# buck.net
KiCad netlist of a schematic drawn in EAGLE
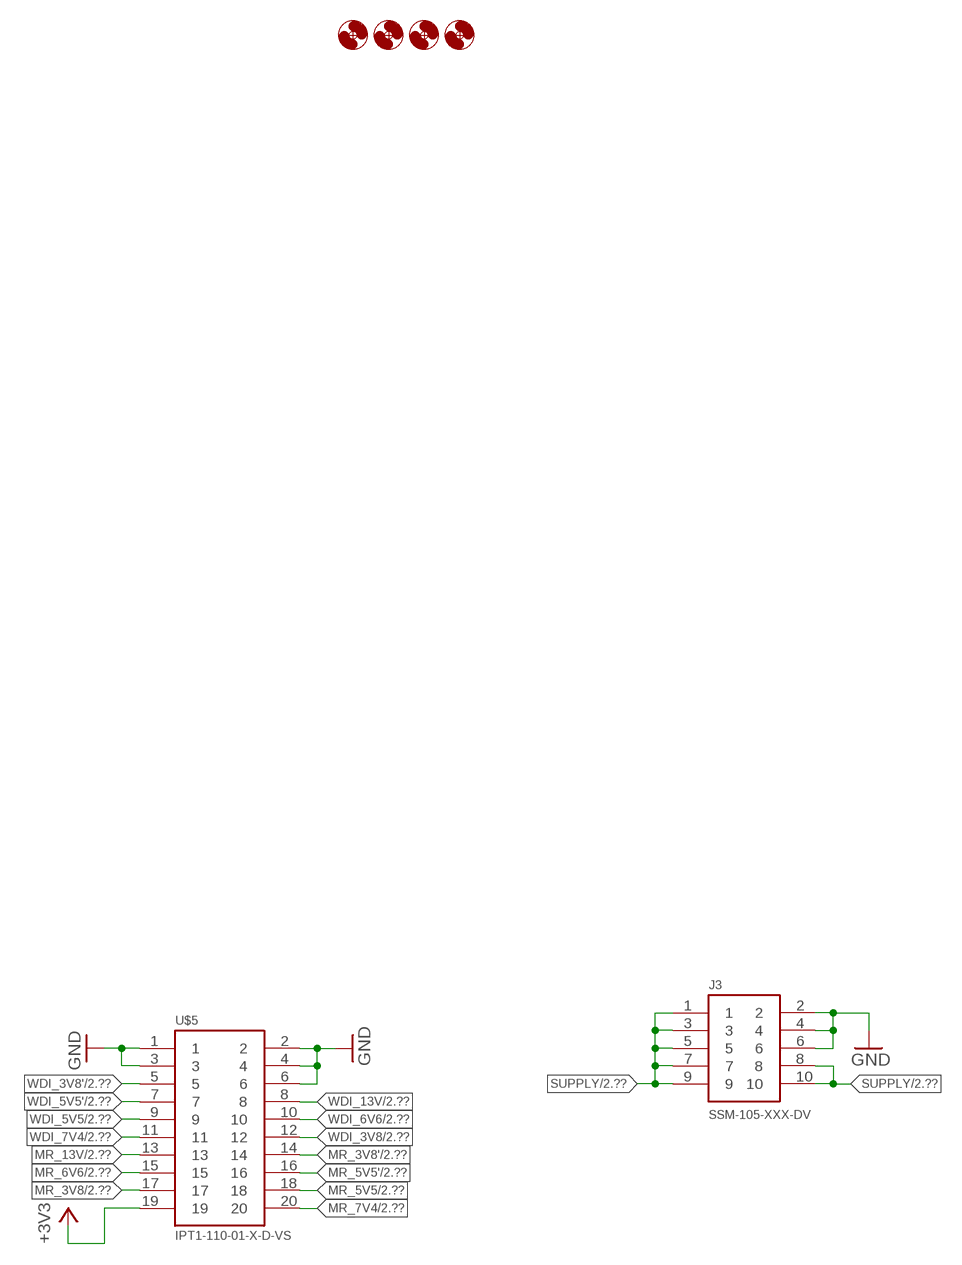
[diagram p0: schematic, sheet 1]
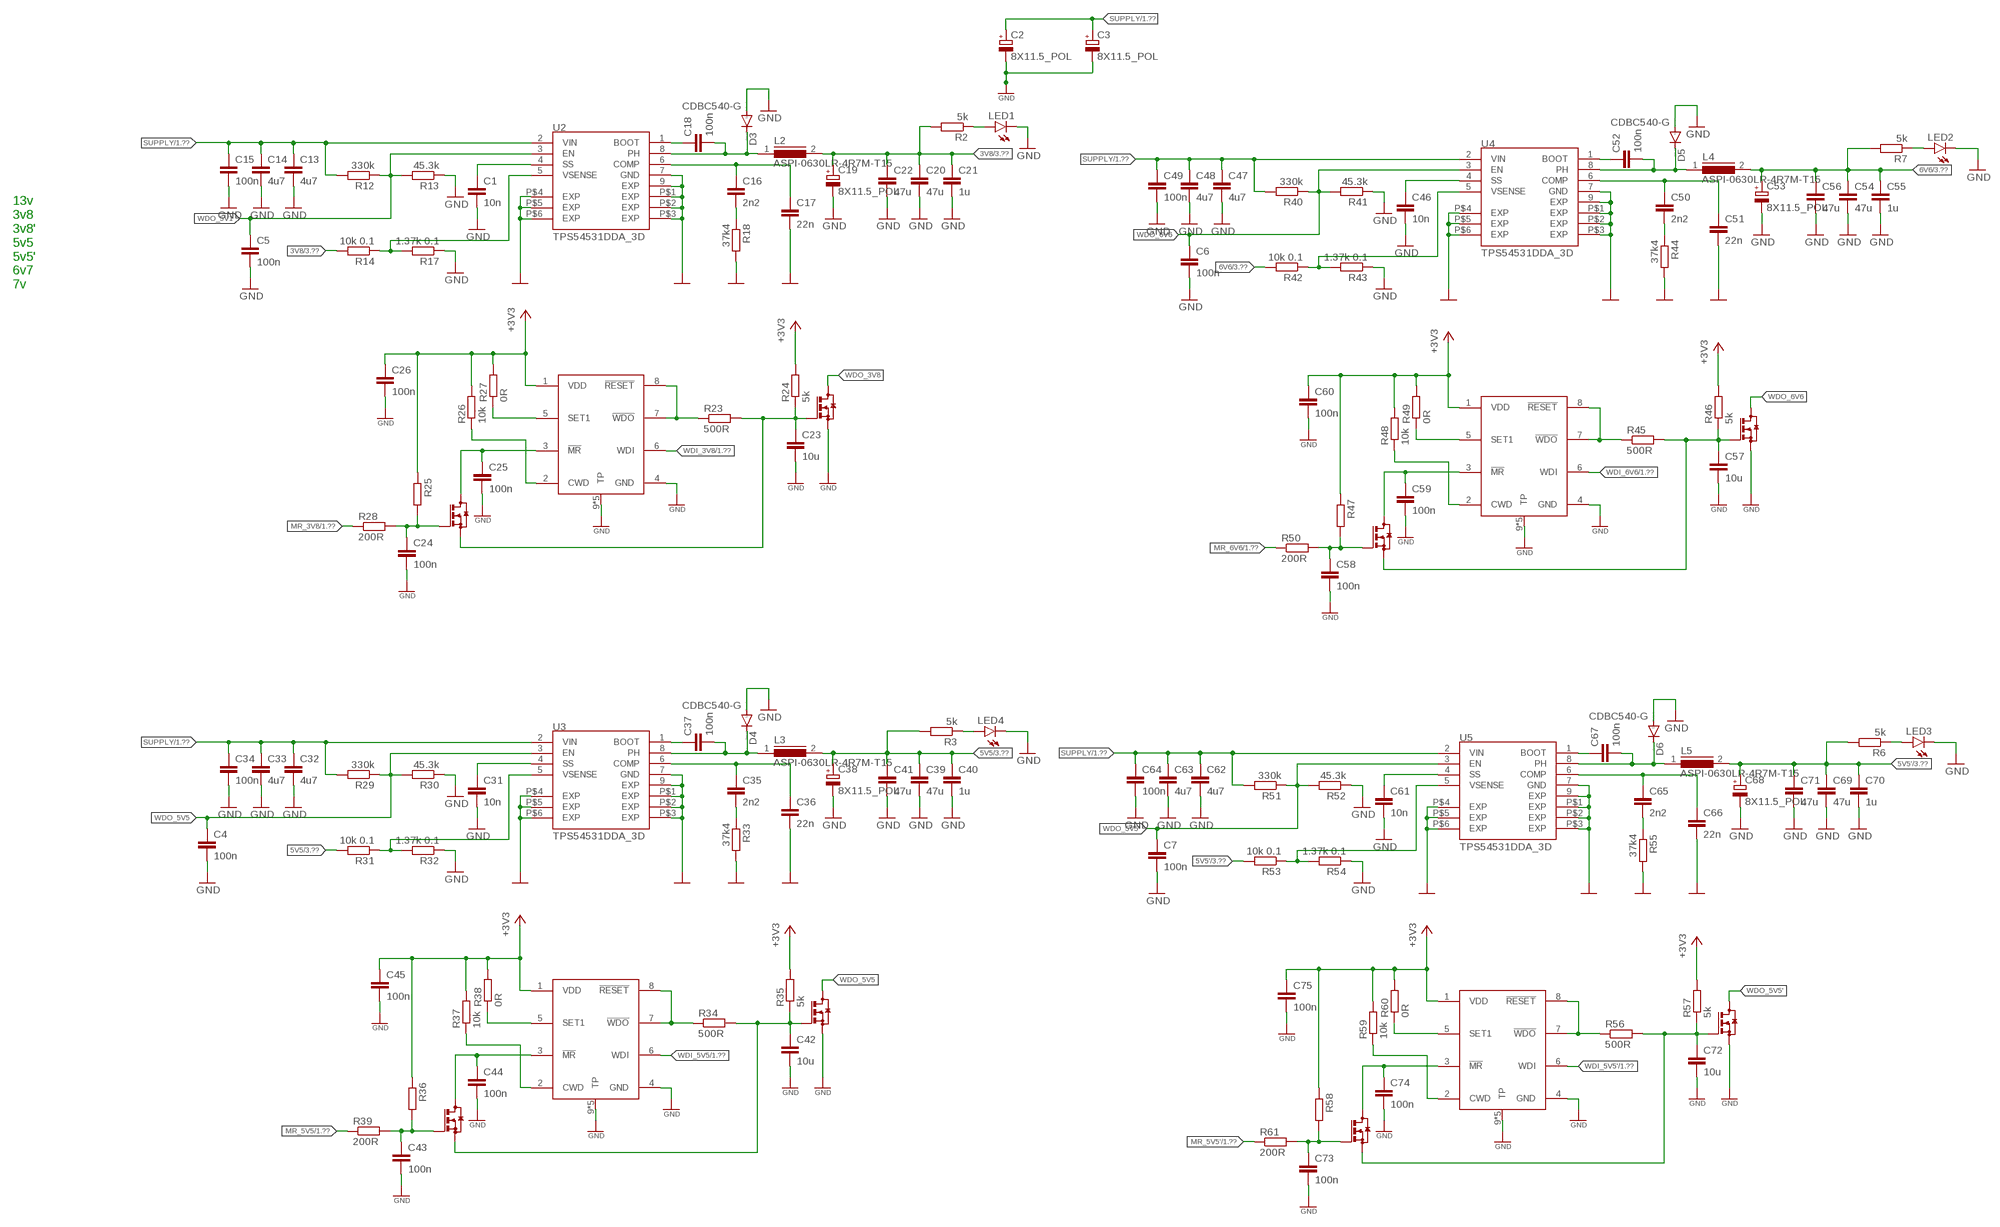
[diagram p1: schematic, sheet 2, part 1 of 2]
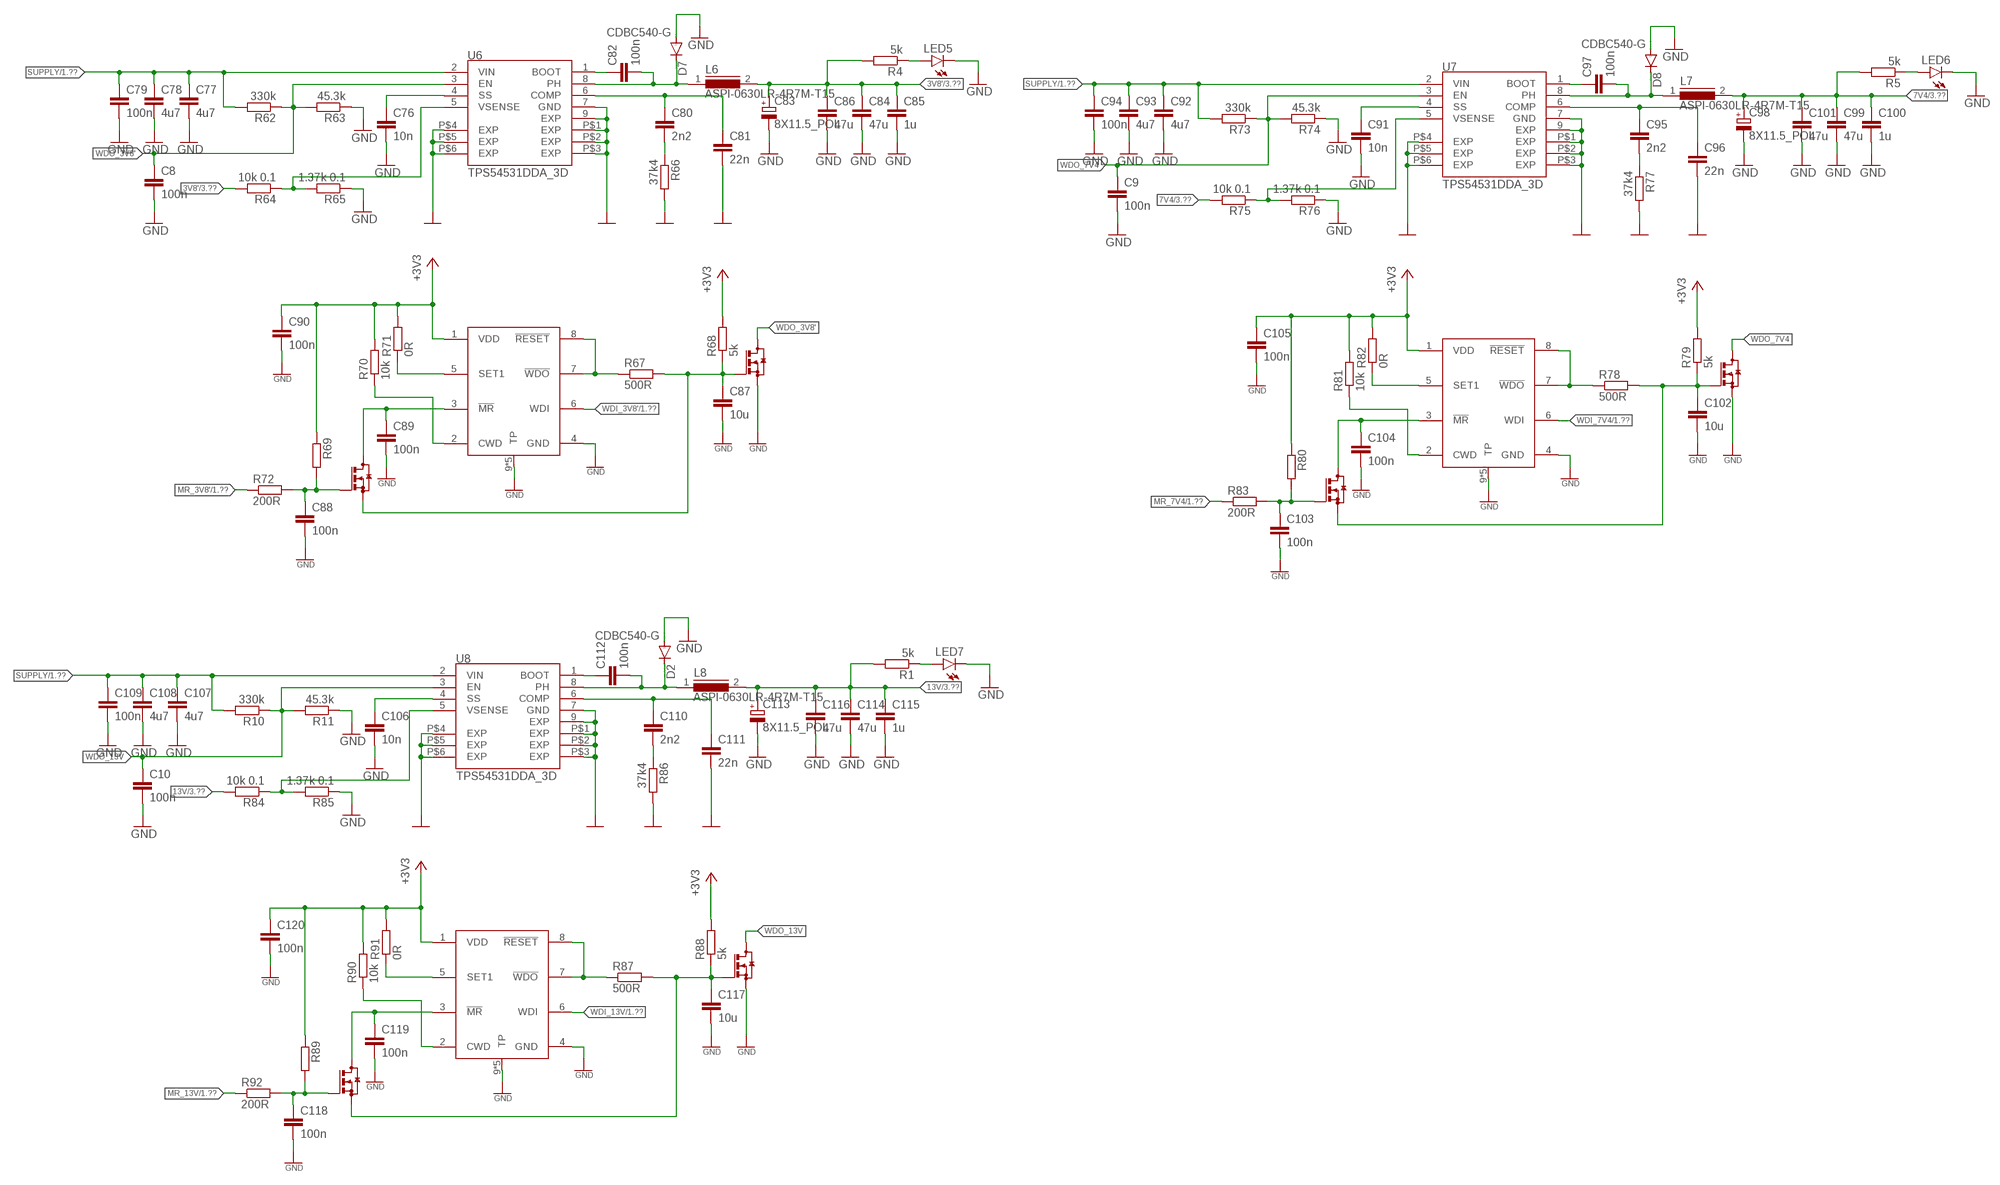
[diagram p2: schematic, sheet 2, part 2 of 2]
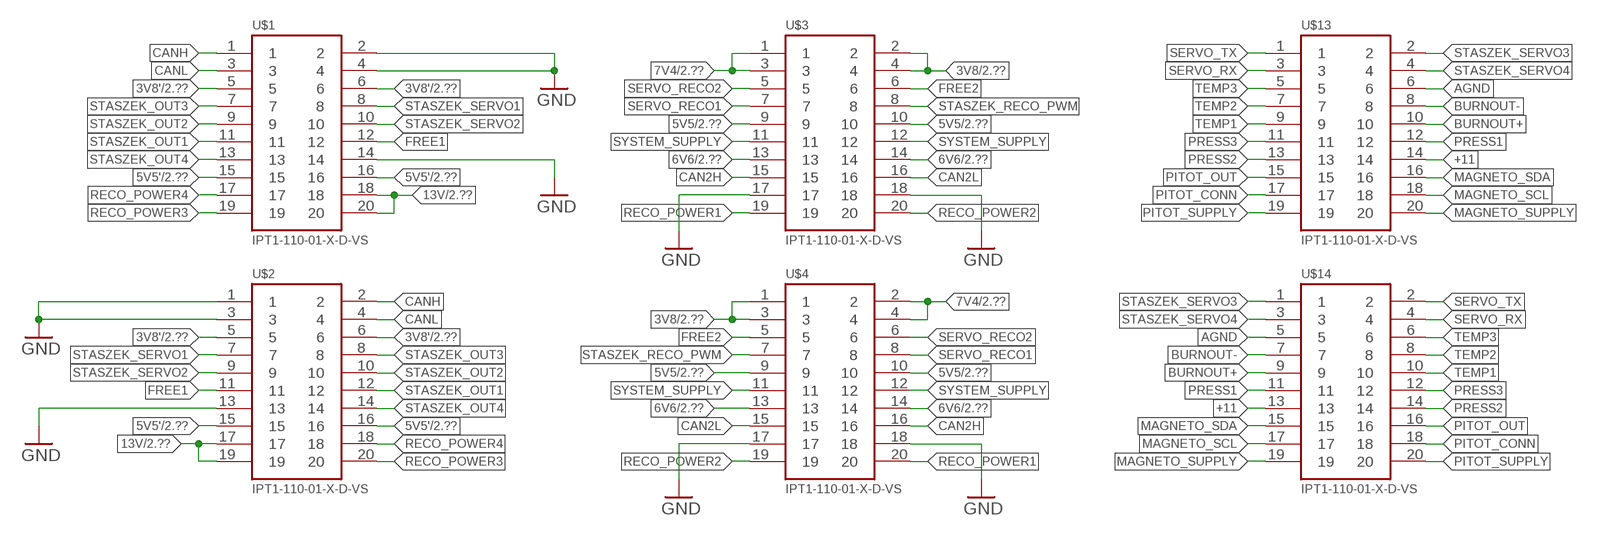
[diagram p3: schematic, sheet 3]

(export (version "E")
  (design (tool "Eeschema 10.0.6"))
  (components
    (comp (ref "U$1")
      (value "IPT1-110-01-X-D-VS")
      (footprint "eagle-import:IPT1-110-01-X-D-VS")
      (fields (field (name "MF") "Samtec") (field (name "MP") "IPT1-110--01-S-D-VS-"))
      (libsource (lib "eagle-import") (part "IPT1-110-01-X-D-VS"))
    )
    (comp (ref "U$2")
      (value "IPT1-110-01-X-D-VS")
      (footprint "eagle-import:IPT1-110-01-X-D-VS")
      (fields (field (name "MF") "Samtec") (field (name "MP") "IPT1-110--01-S-D-VS-"))
      (libsource (lib "eagle-import") (part "IPT1-110-01-X-D-VS"))
    )
    (comp (ref "U$3")
      (value "IPT1-110-01-X-D-VS")
      (footprint "eagle-import:IPT1-110-01-X-D-VS")
      (fields (field (name "MF") "Samtec") (field (name "MP") "IPT1-110--01-S-D-VS-"))
      (libsource (lib "eagle-import") (part "IPT1-110-01-X-D-VS"))
    )
    (comp (ref "U$4")
      (value "IPT1-110-01-X-D-VS")
      (footprint "eagle-import:IPT1-110-01-X-D-VS")
      (fields (field (name "MF") "Samtec") (field (name "MP") "IPT1-110--01-S-D-VS-"))
      (libsource (lib "eagle-import") (part "IPT1-110-01-X-D-VS"))
    )
    (comp (ref "U$13")
      (value "IPT1-110-01-X-D-VS")
      (footprint "eagle-import:IPT1-110-01-X-D-VS")
      (fields (field (name "MF") "Samtec") (field (name "MP") "IPT1-110--01-S-D-VS-"))
      (libsource (lib "eagle-import") (part "IPT1-110-01-X-D-VS"))
    )
    (comp (ref "U$14")
      (value "IPT1-110-01-X-D-VS")
      (footprint "eagle-import:IPT1-110-01-X-D-VS")
      (fields (field (name "MF") "Samtec") (field (name "MP") "IPT1-110--01-S-D-VS-"))
      (libsource (lib "eagle-import") (part "IPT1-110-01-X-D-VS"))
    )
    (comp (ref "H1")
      (value "MOUNT-HOLE3.2")
      (footprint "eagle-import:3,2")
      (libsource (lib "eagle-import") (part "MOUNT-HOLE3.2"))
    )
    (comp (ref "H2")
      (value "MOUNT-HOLE3.2")
      (footprint "eagle-import:3,2")
      (libsource (lib "eagle-import") (part "MOUNT-HOLE3.2"))
    )
    (comp (ref "H3")
      (value "MOUNT-HOLE3.2")
      (footprint "eagle-import:3,2")
      (libsource (lib "eagle-import") (part "MOUNT-HOLE3.2"))
    )
    (comp (ref "H4")
      (value "MOUNT-HOLE3.2")
      (footprint "eagle-import:3,2")
      (libsource (lib "eagle-import") (part "MOUNT-HOLE3.2"))
    )
    (comp (ref "J3")
      (value "SSM-105-XXX-DV")
      (footprint "eagle-import:SSM-105-XXX-DV")
      (fields (field (name "MF") "Samtec"))
      (libsource (lib "eagle-import") (part "SSM-105-XXX-DV"))
    )
    (comp (ref "U$5")
      (value "IPT1-110-01-X-D-VS")
      (footprint "eagle-import:IPT1-110-01-X-D-VS")
      (fields (field (name "MF") "Samtec") (field (name "MP") "IPT1-110--01-S-D-VS-"))
      (libsource (lib "eagle-import") (part "IPT1-110-01-X-D-VS"))
    )
    (comp (ref "C1")
      (value "10n")
      (footprint "eagle-import:C0603K")
      (libsource (lib "eagle-import") (part "C-EUC0603K"))
    )
    (comp (ref "C2")
      (value "8X11.5_POL")
      (footprint "eagle-import:CAPPRD350W65D800H1150A")
      (libsource (lib "eagle-import") (part "8X11.5_POL"))
    )
    (comp (ref "C3")
      (value "8X11.5_POL")
      (footprint "eagle-import:CAPPRD350W65D800H1150A")
      (libsource (lib "eagle-import") (part "8X11.5_POL"))
    )
    (comp (ref "C4")
      (value "100n")
      (footprint "eagle-import:C0603K")
      (libsource (lib "eagle-import") (part "C-EUC0603K"))
    )
    (comp (ref "C5")
      (value "100n")
      (footprint "eagle-import:C0603K")
      (libsource (lib "eagle-import") (part "C-EUC0603K"))
    )
    (comp (ref "C6")
      (value "100n")
      (footprint "eagle-import:C0603K")
      (libsource (lib "eagle-import") (part "C-EUC0603K"))
    )
    (comp (ref "C7")
      (value "100n")
      (footprint "eagle-import:C0603K")
      (libsource (lib "eagle-import") (part "C-EUC0603K"))
    )
    (comp (ref "C8")
      (value "100n")
      (footprint "eagle-import:C0603K")
      (libsource (lib "eagle-import") (part "C-EUC0603K"))
    )
    (comp (ref "C9")
      (value "100n")
      (footprint "eagle-import:C0603K")
      (libsource (lib "eagle-import") (part "C-EUC0603K"))
    )
    (comp (ref "C10")
      (value "100n")
      (footprint "eagle-import:C0603K")
      (libsource (lib "eagle-import") (part "C-EUC0603K"))
    )
    (comp (ref "C13")
      (value "4u7")
      (footprint "eagle-import:C0805K")
      (libsource (lib "eagle-import") (part "C-EUC0805K"))
    )
    (comp (ref "C14")
      (value "4u7")
      (footprint "eagle-import:C0805K")
      (libsource (lib "eagle-import") (part "C-EUC0805K"))
    )
    (comp (ref "C15")
      (value "100n")
      (footprint "eagle-import:C0603K")
      (libsource (lib "eagle-import") (part "C-EUC0603K"))
    )
    (comp (ref "C16")
      (value "2n2")
      (footprint "eagle-import:C0603K")
      (libsource (lib "eagle-import") (part "C-EUC0603K"))
    )
    (comp (ref "C17")
      (value "22n")
      (footprint "eagle-import:C0603K")
      (libsource (lib "eagle-import") (part "C-EUC0603K"))
    )
    (comp (ref "C18")
      (value "100n")
      (footprint "eagle-import:C0603K")
      (libsource (lib "eagle-import") (part "C-EUC0603K"))
    )
    (comp (ref "C19")
      (value "8X11.5_POL")
      (footprint "eagle-import:CAPPRD350W65D800H1150A")
      (libsource (lib "eagle-import") (part "8X11.5_POL"))
    )
    (comp (ref "C20")
      (value "47u")
      (footprint "eagle-import:C1210")
      (libsource (lib "eagle-import") (part "C-EUC1210"))
    )
    (comp (ref "C21")
      (value "1u")
      (footprint "eagle-import:C0603K")
      (libsource (lib "eagle-import") (part "C-EUC0603K"))
    )
    (comp (ref "C22")
      (value "47u")
      (footprint "eagle-import:C1210")
      (libsource (lib "eagle-import") (part "C-EUC1210"))
    )
    (comp (ref "C23")
      (value "10u")
      (footprint "eagle-import:C0805K")
      (libsource (lib "eagle-import") (part "C-EUC0805K"))
    )
    (comp (ref "C24")
      (value "100n")
      (footprint "eagle-import:C0603K")
      (libsource (lib "eagle-import") (part "C-EUC0603K"))
    )
    (comp (ref "C25")
      (value "100n")
      (footprint "eagle-import:C0603K")
      (libsource (lib "eagle-import") (part "C-EUC0603K"))
    )
    (comp (ref "C26")
      (value "100n")
      (footprint "eagle-import:C0603K")
      (libsource (lib "eagle-import") (part "C-EUC0603K"))
    )
    (comp (ref "C31")
      (value "10n")
      (footprint "eagle-import:C0603K")
      (libsource (lib "eagle-import") (part "C-EUC0603K"))
    )
    (comp (ref "C32")
      (value "4u7")
      (footprint "eagle-import:C0805K")
      (libsource (lib "eagle-import") (part "C-EUC0805K"))
    )
    (comp (ref "C33")
      (value "4u7")
      (footprint "eagle-import:C0805K")
      (libsource (lib "eagle-import") (part "C-EUC0805K"))
    )
    (comp (ref "C34")
      (value "100n")
      (footprint "eagle-import:C0603K")
      (libsource (lib "eagle-import") (part "C-EUC0603K"))
    )
    (comp (ref "C35")
      (value "2n2")
      (footprint "eagle-import:C0603K")
      (libsource (lib "eagle-import") (part "C-EUC0603K"))
    )
    (comp (ref "C36")
      (value "22n")
      (footprint "eagle-import:C0603K")
      (libsource (lib "eagle-import") (part "C-EUC0603K"))
    )
    (comp (ref "C37")
      (value "100n")
      (footprint "eagle-import:C0603K")
      (libsource (lib "eagle-import") (part "C-EUC0603K"))
    )
    (comp (ref "C38")
      (value "8X11.5_POL")
      (footprint "eagle-import:CAPPRD350W65D800H1150A")
      (libsource (lib "eagle-import") (part "8X11.5_POL"))
    )
    (comp (ref "C39")
      (value "47u")
      (footprint "eagle-import:C1210")
      (libsource (lib "eagle-import") (part "C-EUC1210"))
    )
    (comp (ref "C40")
      (value "1u")
      (footprint "eagle-import:C0603K")
      (libsource (lib "eagle-import") (part "C-EUC0603K"))
    )
    (comp (ref "C41")
      (value "47u")
      (footprint "eagle-import:C1210")
      (libsource (lib "eagle-import") (part "C-EUC1210"))
    )
    (comp (ref "C42")
      (value "10u")
      (footprint "eagle-import:C0805K")
      (libsource (lib "eagle-import") (part "C-EUC0805K"))
    )
    (comp (ref "C43")
      (value "100n")
      (footprint "eagle-import:C0603K")
      (libsource (lib "eagle-import") (part "C-EUC0603K"))
    )
    (comp (ref "C44")
      (value "100n")
      (footprint "eagle-import:C0603K")
      (libsource (lib "eagle-import") (part "C-EUC0603K"))
    )
    (comp (ref "C45")
      (value "100n")
      (footprint "eagle-import:C0603K")
      (libsource (lib "eagle-import") (part "C-EUC0603K"))
    )
    (comp (ref "C46")
      (value "10n")
      (footprint "eagle-import:C0603K")
      (libsource (lib "eagle-import") (part "C-EUC0603K"))
    )
    (comp (ref "C47")
      (value "4u7")
      (footprint "eagle-import:C0805K")
      (libsource (lib "eagle-import") (part "C-EUC0805K"))
    )
    (comp (ref "C48")
      (value "4u7")
      (footprint "eagle-import:C0805K")
      (libsource (lib "eagle-import") (part "C-EUC0805K"))
    )
    (comp (ref "C49")
      (value "100n")
      (footprint "eagle-import:C0603K")
      (libsource (lib "eagle-import") (part "C-EUC0603K"))
    )
    (comp (ref "C50")
      (value "2n2")
      (footprint "eagle-import:C0603K")
      (libsource (lib "eagle-import") (part "C-EUC0603K"))
    )
    (comp (ref "C51")
      (value "22n")
      (footprint "eagle-import:C0603K")
      (libsource (lib "eagle-import") (part "C-EUC0603K"))
    )
    (comp (ref "C52")
      (value "100n")
      (footprint "eagle-import:C0603K")
      (libsource (lib "eagle-import") (part "C-EUC0603K"))
    )
    (comp (ref "C53")
      (value "8X11.5_POL")
      (footprint "eagle-import:CAPPRD350W65D800H1150A")
      (libsource (lib "eagle-import") (part "8X11.5_POL"))
    )
    (comp (ref "C54")
      (value "47u")
      (footprint "eagle-import:C1210")
      (libsource (lib "eagle-import") (part "C-EUC1210"))
    )
    (comp (ref "C55")
      (value "1u")
      (footprint "eagle-import:C0603K")
      (libsource (lib "eagle-import") (part "C-EUC0603K"))
    )
    (comp (ref "C56")
      (value "47u")
      (footprint "eagle-import:C1210")
      (libsource (lib "eagle-import") (part "C-EUC1210"))
    )
    (comp (ref "C57")
      (value "10u")
      (footprint "eagle-import:C0805K")
      (libsource (lib "eagle-import") (part "C-EUC0805K"))
    )
    (comp (ref "C58")
      (value "100n")
      (footprint "eagle-import:C0603K")
      (libsource (lib "eagle-import") (part "C-EUC0603K"))
    )
    (comp (ref "C59")
      (value "100n")
      (footprint "eagle-import:C0603K")
      (libsource (lib "eagle-import") (part "C-EUC0603K"))
    )
    (comp (ref "C60")
      (value "100n")
      (footprint "eagle-import:C0603K")
      (libsource (lib "eagle-import") (part "C-EUC0603K"))
    )
    (comp (ref "C61")
      (value "10n")
      (footprint "eagle-import:C0603K")
      (libsource (lib "eagle-import") (part "C-EUC0603K"))
    )
    (comp (ref "C62")
      (value "4u7")
      (footprint "eagle-import:C0805K")
      (libsource (lib "eagle-import") (part "C-EUC0805K"))
    )
    (comp (ref "C63")
      (value "4u7")
      (footprint "eagle-import:C0805K")
      (libsource (lib "eagle-import") (part "C-EUC0805K"))
    )
    (comp (ref "C64")
      (value "100n")
      (footprint "eagle-import:C0603K")
      (libsource (lib "eagle-import") (part "C-EUC0603K"))
    )
    (comp (ref "C65")
      (value "2n2")
      (footprint "eagle-import:C0603K")
      (libsource (lib "eagle-import") (part "C-EUC0603K"))
    )
    (comp (ref "C66")
      (value "22n")
      (footprint "eagle-import:C0603K")
      (libsource (lib "eagle-import") (part "C-EUC0603K"))
    )
    (comp (ref "C67")
      (value "100n")
      (footprint "eagle-import:C0603K")
      (libsource (lib "eagle-import") (part "C-EUC0603K"))
    )
    (comp (ref "C68")
      (value "8X11.5_POL")
      (footprint "eagle-import:CAPPRD350W65D800H1150A")
      (libsource (lib "eagle-import") (part "8X11.5_POL"))
    )
    (comp (ref "C69")
      (value "47u")
      (footprint "eagle-import:C1210")
      (libsource (lib "eagle-import") (part "C-EUC1210"))
    )
    (comp (ref "C70")
      (value "1u")
      (footprint "eagle-import:C0603K")
      (libsource (lib "eagle-import") (part "C-EUC0603K"))
    )
    (comp (ref "C71")
      (value "47u")
      (footprint "eagle-import:C1210")
      (libsource (lib "eagle-import") (part "C-EUC1210"))
    )
    (comp (ref "C72")
      (value "10u")
      (footprint "eagle-import:C0805K")
      (libsource (lib "eagle-import") (part "C-EUC0805K"))
    )
    (comp (ref "C73")
      (value "100n")
      (footprint "eagle-import:C0603K")
      (libsource (lib "eagle-import") (part "C-EUC0603K"))
    )
    (comp (ref "C74")
      (value "100n")
      (footprint "eagle-import:C0603K")
      (libsource (lib "eagle-import") (part "C-EUC0603K"))
    )
    (comp (ref "C75")
      (value "100n")
      (footprint "eagle-import:C0603K")
      (libsource (lib "eagle-import") (part "C-EUC0603K"))
    )
    (comp (ref "C76")
      (value "10n")
      (footprint "eagle-import:C0603K")
      (libsource (lib "eagle-import") (part "C-EUC0603K"))
    )
    (comp (ref "C77")
      (value "4u7")
      (footprint "eagle-import:C0805K")
      (libsource (lib "eagle-import") (part "C-EUC0805K"))
    )
    (comp (ref "C78")
      (value "4u7")
      (footprint "eagle-import:C0805K")
      (libsource (lib "eagle-import") (part "C-EUC0805K"))
    )
    (comp (ref "C79")
      (value "100n")
      (footprint "eagle-import:C0603K")
      (libsource (lib "eagle-import") (part "C-EUC0603K"))
    )
    (comp (ref "C80")
      (value "2n2")
      (footprint "eagle-import:C0603K")
      (libsource (lib "eagle-import") (part "C-EUC0603K"))
    )
    (comp (ref "C81")
      (value "22n")
      (footprint "eagle-import:C0603K")
      (libsource (lib "eagle-import") (part "C-EUC0603K"))
    )
    (comp (ref "C82")
      (value "100n")
      (footprint "eagle-import:C0603K")
      (libsource (lib "eagle-import") (part "C-EUC0603K"))
    )
    (comp (ref "C83")
      (value "8X11.5_POL")
      (footprint "eagle-import:CAPPRD350W65D800H1150A")
      (libsource (lib "eagle-import") (part "8X11.5_POL"))
    )
    (comp (ref "C84")
      (value "47u")
      (footprint "eagle-import:C1210")
      (libsource (lib "eagle-import") (part "C-EUC1210"))
    )
    (comp (ref "C85")
      (value "1u")
      (footprint "eagle-import:C0603K")
      (libsource (lib "eagle-import") (part "C-EUC0603K"))
    )
    (comp (ref "C86")
      (value "47u")
      (footprint "eagle-import:C1210")
      (libsource (lib "eagle-import") (part "C-EUC1210"))
    )
    (comp (ref "C87")
      (value "10u")
      (footprint "eagle-import:C0805K")
      (libsource (lib "eagle-import") (part "C-EUC0805K"))
    )
    (comp (ref "C88")
      (value "100n")
      (footprint "eagle-import:C0603K")
      (libsource (lib "eagle-import") (part "C-EUC0603K"))
    )
    (comp (ref "C89")
      (value "100n")
      (footprint "eagle-import:C0603K")
      (libsource (lib "eagle-import") (part "C-EUC0603K"))
    )
    (comp (ref "C90")
      (value "100n")
      (footprint "eagle-import:C0603K")
      (libsource (lib "eagle-import") (part "C-EUC0603K"))
    )
    (comp (ref "C91")
      (value "10n")
      (footprint "eagle-import:C0603K")
      (libsource (lib "eagle-import") (part "C-EUC0603K"))
    )
    (comp (ref "C92")
      (value "4u7")
      (footprint "eagle-import:C0805K")
      (libsource (lib "eagle-import") (part "C-EUC0805K"))
    )
    (comp (ref "C93")
      (value "4u7")
      (footprint "eagle-import:C0805K")
      (libsource (lib "eagle-import") (part "C-EUC0805K"))
    )
    (comp (ref "C94")
      (value "100n")
      (footprint "eagle-import:C0603K")
      (libsource (lib "eagle-import") (part "C-EUC0603K"))
    )
    (comp (ref "C95")
      (value "2n2")
      (footprint "eagle-import:C0603K")
      (libsource (lib "eagle-import") (part "C-EUC0603K"))
    )
    (comp (ref "C96")
      (value "22n")
      (footprint "eagle-import:C0603K")
      (libsource (lib "eagle-import") (part "C-EUC0603K"))
    )
    (comp (ref "C97")
      (value "100n")
      (footprint "eagle-import:C0603K")
      (libsource (lib "eagle-import") (part "C-EUC0603K"))
    )
    (comp (ref "C98")
      (value "8X11.5_POL")
      (footprint "eagle-import:CAPPRD350W65D800H1150A")
      (libsource (lib "eagle-import") (part "8X11.5_POL"))
    )
    (comp (ref "C99")
      (value "47u")
      (footprint "eagle-import:C1210")
      (libsource (lib "eagle-import") (part "C-EUC1210"))
    )
    (comp (ref "C100")
      (value "1u")
      (footprint "eagle-import:C0603K")
      (libsource (lib "eagle-import") (part "C-EUC0603K"))
    )
    (comp (ref "C101")
      (value "47u")
      (footprint "eagle-import:C1210")
      (libsource (lib "eagle-import") (part "C-EUC1210"))
    )
    (comp (ref "C102")
      (value "10u")
      (footprint "eagle-import:C0805K")
      (libsource (lib "eagle-import") (part "C-EUC0805K"))
    )
    (comp (ref "C103")
      (value "100n")
      (footprint "eagle-import:C0603K")
      (libsource (lib "eagle-import") (part "C-EUC0603K"))
    )
    (comp (ref "C104")
      (value "100n")
      (footprint "eagle-import:C0603K")
      (libsource (lib "eagle-import") (part "C-EUC0603K"))
    )
    (comp (ref "C105")
      (value "100n")
      (footprint "eagle-import:C0603K")
      (libsource (lib "eagle-import") (part "C-EUC0603K"))
    )
    (comp (ref "C106")
      (value "10n")
      (footprint "eagle-import:C0603K")
      (libsource (lib "eagle-import") (part "C-EUC0603K"))
    )
    (comp (ref "C107")
      (value "4u7")
      (footprint "eagle-import:C0805K")
      (libsource (lib "eagle-import") (part "C-EUC0805K"))
    )
    (comp (ref "C108")
      (value "4u7")
      (footprint "eagle-import:C0805K")
      (libsource (lib "eagle-import") (part "C-EUC0805K"))
    )
    (comp (ref "C109")
      (value "100n")
      (footprint "eagle-import:C0603K")
      (libsource (lib "eagle-import") (part "C-EUC0603K"))
    )
    (comp (ref "C110")
      (value "2n2")
      (footprint "eagle-import:C0603K")
      (libsource (lib "eagle-import") (part "C-EUC0603K"))
    )
    (comp (ref "C111")
      (value "22n")
      (footprint "eagle-import:C0603K")
      (libsource (lib "eagle-import") (part "C-EUC0603K"))
    )
    (comp (ref "C112")
      (value "100n")
      (footprint "eagle-import:C0603K")
      (libsource (lib "eagle-import") (part "C-EUC0603K"))
    )
    (comp (ref "C113")
      (value "8X11.5_POL")
      (footprint "eagle-import:CAPPRD350W65D800H1150A")
      (libsource (lib "eagle-import") (part "8X11.5_POL"))
    )
    (comp (ref "C114")
      (value "47u")
      (footprint "eagle-import:C1210")
      (libsource (lib "eagle-import") (part "C-EUC1210"))
    )
    (comp (ref "C115")
      (value "1u")
      (footprint "eagle-import:C0603K")
      (libsource (lib "eagle-import") (part "C-EUC0603K"))
    )
    (comp (ref "C116")
      (value "47u")
      (footprint "eagle-import:C1210")
      (libsource (lib "eagle-import") (part "C-EUC1210"))
    )
    (comp (ref "C117")
      (value "10u")
      (footprint "eagle-import:C0805K")
      (libsource (lib "eagle-import") (part "C-EUC0805K"))
    )
    (comp (ref "C118")
      (value "100n")
      (footprint "eagle-import:C0603K")
      (libsource (lib "eagle-import") (part "C-EUC0603K"))
    )
    (comp (ref "C119")
      (value "100n")
      (footprint "eagle-import:C0603K")
      (libsource (lib "eagle-import") (part "C-EUC0603K"))
    )
    (comp (ref "C120")
      (value "100n")
      (footprint "eagle-import:C0603K")
      (libsource (lib "eagle-import") (part "C-EUC0603K"))
    )
    (comp (ref "D2")
      (value "CDBC540-G")
      (footprint "eagle-import:SMC")
      (libsource (lib "eagle-import") (part "DIODE-SMC"))
    )
    (comp (ref "D3")
      (value "CDBC540-G")
      (footprint "eagle-import:SMC")
      (libsource (lib "eagle-import") (part "DIODE-SMC"))
    )
    (comp (ref "D4")
      (value "CDBC540-G")
      (footprint "eagle-import:SMC")
      (libsource (lib "eagle-import") (part "DIODE-SMC"))
    )
    (comp (ref "D5")
      (value "CDBC540-G")
      (footprint "eagle-import:SMC")
      (libsource (lib "eagle-import") (part "DIODE-SMC"))
    )
    (comp (ref "D6")
      (value "CDBC540-G")
      (footprint "eagle-import:SMC")
      (libsource (lib "eagle-import") (part "DIODE-SMC"))
    )
    (comp (ref "D7")
      (value "CDBC540-G")
      (footprint "eagle-import:SMC")
      (libsource (lib "eagle-import") (part "DIODE-SMC"))
    )
    (comp (ref "D8")
      (value "CDBC540-G")
      (footprint "eagle-import:SMC")
      (libsource (lib "eagle-import") (part "DIODE-SMC"))
    )
    (comp (ref "L2")
      (value "ASPI-0630LR-4R7M-T15")
      (footprint "eagle-import:DR74")
      (libsource (lib "eagle-import") (part "DR74"))
    )
    (comp (ref "L3")
      (value "ASPI-0630LR-4R7M-T15")
      (footprint "eagle-import:DR74")
      (libsource (lib "eagle-import") (part "DR74"))
    )
    (comp (ref "L4")
      (value "ASPI-0630LR-4R7M-T15")
      (footprint "eagle-import:DR74")
      (libsource (lib "eagle-import") (part "DR74"))
    )
    (comp (ref "L5")
      (value "ASPI-0630LR-4R7M-T15")
      (footprint "eagle-import:DR74")
      (libsource (lib "eagle-import") (part "DR74"))
    )
    (comp (ref "L6")
      (value "ASPI-0630LR-4R7M-T15")
      (footprint "eagle-import:DR74")
      (libsource (lib "eagle-import") (part "DR74"))
    )
    (comp (ref "L7")
      (value "ASPI-0630LR-4R7M-T15")
      (footprint "eagle-import:DR74")
      (libsource (lib "eagle-import") (part "DR74"))
    )
    (comp (ref "L8")
      (value "ASPI-0630LR-4R7M-T15")
      (footprint "eagle-import:DR74")
      (libsource (lib "eagle-import") (part "DR74"))
    )
    (comp (ref "LED1")
      (value "LEDCHIPLED_0603")
      (footprint "eagle-import:CHIPLED_0603")
      (libsource (lib "eagle-import") (part "LEDCHIPLED_0603"))
    )
    (comp (ref "LED2")
      (value "LEDCHIPLED_0603")
      (footprint "eagle-import:CHIPLED_0603")
      (libsource (lib "eagle-import") (part "LEDCHIPLED_0603"))
    )
    (comp (ref "LED3")
      (value "LEDCHIPLED_0603")
      (footprint "eagle-import:CHIPLED_0603")
      (libsource (lib "eagle-import") (part "LEDCHIPLED_0603"))
    )
    (comp (ref "LED4")
      (value "LEDCHIPLED_0603")
      (footprint "eagle-import:CHIPLED_0603")
      (libsource (lib "eagle-import") (part "LEDCHIPLED_0603"))
    )
    (comp (ref "LED5")
      (value "LEDCHIPLED_0603")
      (footprint "eagle-import:CHIPLED_0603")
      (libsource (lib "eagle-import") (part "LEDCHIPLED_0603"))
    )
    (comp (ref "LED6")
      (value "LEDCHIPLED_0603")
      (footprint "eagle-import:CHIPLED_0603")
      (libsource (lib "eagle-import") (part "LEDCHIPLED_0603"))
    )
    (comp (ref "LED7")
      (value "LEDCHIPLED_0603")
      (footprint "eagle-import:CHIPLED_0603")
      (libsource (lib "eagle-import") (part "LEDCHIPLED_0603"))
    )
    (comp (ref "Q1")
      (value "BSS123")
      (footprint "eagle-import:SOT23")
      (fields (field (name "SPICEPREFIX") "Q"))
      (libsource (lib "eagle-import") (part "BSS123"))
    )
    (comp (ref "Q2")
      (value "BSS123")
      (footprint "eagle-import:SOT23")
      (libsource (lib "eagle-import") (part "BSS123"))
    )
    (comp (ref "Q5")
      (value "BSS123")
      (footprint "eagle-import:SOT23")
      (fields (field (name "SPICEPREFIX") "Q"))
      (libsource (lib "eagle-import") (part "BSS123"))
    )
    (comp (ref "Q6")
      (value "BSS123")
      (footprint "eagle-import:SOT23")
      (libsource (lib "eagle-import") (part "BSS123"))
    )
    (comp (ref "Q7")
      (value "BSS123")
      (footprint "eagle-import:SOT23")
      (fields (field (name "SPICEPREFIX") "Q"))
      (libsource (lib "eagle-import") (part "BSS123"))
    )
    (comp (ref "Q8")
      (value "BSS123")
      (footprint "eagle-import:SOT23")
      (libsource (lib "eagle-import") (part "BSS123"))
    )
    (comp (ref "Q9")
      (value "BSS123")
      (footprint "eagle-import:SOT23")
      (fields (field (name "SPICEPREFIX") "Q"))
      (libsource (lib "eagle-import") (part "BSS123"))
    )
    (comp (ref "Q10")
      (value "BSS123")
      (footprint "eagle-import:SOT23")
      (libsource (lib "eagle-import") (part "BSS123"))
    )
    (comp (ref "Q11")
      (value "BSS123")
      (footprint "eagle-import:SOT23")
      (fields (field (name "SPICEPREFIX") "Q"))
      (libsource (lib "eagle-import") (part "BSS123"))
    )
    (comp (ref "Q12")
      (value "BSS123")
      (footprint "eagle-import:SOT23")
      (libsource (lib "eagle-import") (part "BSS123"))
    )
    (comp (ref "Q13")
      (value "BSS123")
      (footprint "eagle-import:SOT23")
      (fields (field (name "SPICEPREFIX") "Q"))
      (libsource (lib "eagle-import") (part "BSS123"))
    )
    (comp (ref "Q14")
      (value "BSS123")
      (footprint "eagle-import:SOT23")
      (libsource (lib "eagle-import") (part "BSS123"))
    )
    (comp (ref "Q15")
      (value "BSS123")
      (footprint "eagle-import:SOT23")
      (fields (field (name "SPICEPREFIX") "Q"))
      (libsource (lib "eagle-import") (part "BSS123"))
    )
    (comp (ref "Q16")
      (value "BSS123")
      (footprint "eagle-import:SOT23")
      (libsource (lib "eagle-import") (part "BSS123"))
    )
    (comp (ref "R1")
      (value "5k")
      (footprint "eagle-import:R0603")
      (libsource (lib "eagle-import") (part "R-EU_R0603"))
    )
    (comp (ref "R2")
      (value "5k")
      (footprint "eagle-import:R0603")
      (libsource (lib "eagle-import") (part "R-EU_R0603"))
    )
    (comp (ref "R3")
      (value "5k")
      (footprint "eagle-import:R0603")
      (libsource (lib "eagle-import") (part "R-EU_R0603"))
    )
    (comp (ref "R4")
      (value "5k")
      (footprint "eagle-import:R0603")
      (libsource (lib "eagle-import") (part "R-EU_R0603"))
    )
    (comp (ref "R5")
      (value "5k")
      (footprint "eagle-import:R0603")
      (libsource (lib "eagle-import") (part "R-EU_R0603"))
    )
    (comp (ref "R6")
      (value "5k")
      (footprint "eagle-import:R0603")
      (libsource (lib "eagle-import") (part "R-EU_R0603"))
    )
    (comp (ref "R7")
      (value "5k")
      (footprint "eagle-import:R0603")
      (libsource (lib "eagle-import") (part "R-EU_R0603"))
    )
    (comp (ref "R10")
      (value "330k")
      (footprint "eagle-import:R0603")
      (libsource (lib "eagle-import") (part "R-EU_R0603"))
    )
    (comp (ref "R11")
      (value "45.3k")
      (footprint "eagle-import:R0603")
      (libsource (lib "eagle-import") (part "R-EU_R0603"))
    )
    (comp (ref "R12")
      (value "330k")
      (footprint "eagle-import:R0603")
      (libsource (lib "eagle-import") (part "R-EU_R0603"))
    )
    (comp (ref "R13")
      (value "45.3k")
      (footprint "eagle-import:R0603")
      (libsource (lib "eagle-import") (part "R-EU_R0603"))
    )
    (comp (ref "R14")
      (value "10k 0.1")
      (footprint "eagle-import:R0603")
      (libsource (lib "eagle-import") (part "R-EU_R0603"))
    )
    (comp (ref "R17")
      (value "1.37k 0.1")
      (footprint "eagle-import:R0603")
      (libsource (lib "eagle-import") (part "R-EU_R0603"))
    )
    (comp (ref "R18")
      (value "37k4")
      (footprint "eagle-import:R0603")
      (libsource (lib "eagle-import") (part "R-EU_R0603"))
    )
    (comp (ref "R23")
      (value "500R")
      (footprint "eagle-import:R0603")
      (libsource (lib "eagle-import") (part "R-EU_R0603"))
    )
    (comp (ref "R24")
      (value "5k")
      (footprint "eagle-import:R0603")
      (libsource (lib "eagle-import") (part "R-EU_R0603"))
    )
    (comp (ref "R25")
      (value "R-EU_R0603")
      (footprint "eagle-import:R0603")
      (libsource (lib "eagle-import") (part "R-EU_R0603"))
    )
    (comp (ref "R26")
      (value "10k")
      (footprint "eagle-import:R0603")
      (libsource (lib "eagle-import") (part "R-EU_R0603"))
    )
    (comp (ref "R27")
      (value "0R")
      (footprint "eagle-import:R0603")
      (libsource (lib "eagle-import") (part "R-EU_R0603"))
    )
    (comp (ref "R28")
      (value "200R")
      (footprint "eagle-import:R0603")
      (libsource (lib "eagle-import") (part "R-EU_R0603"))
    )
    (comp (ref "R29")
      (value "330k")
      (footprint "eagle-import:R0603")
      (libsource (lib "eagle-import") (part "R-EU_R0603"))
    )
    (comp (ref "R30")
      (value "45.3k")
      (footprint "eagle-import:R0603")
      (libsource (lib "eagle-import") (part "R-EU_R0603"))
    )
    (comp (ref "R31")
      (value "10k 0.1")
      (footprint "eagle-import:R0603")
      (libsource (lib "eagle-import") (part "R-EU_R0603"))
    )
    (comp (ref "R32")
      (value "1.37k 0.1")
      (footprint "eagle-import:R0603")
      (libsource (lib "eagle-import") (part "R-EU_R0603"))
    )
    (comp (ref "R33")
      (value "37k4")
      (footprint "eagle-import:R0603")
      (libsource (lib "eagle-import") (part "R-EU_R0603"))
    )
    (comp (ref "R34")
      (value "500R")
      (footprint "eagle-import:R0603")
      (libsource (lib "eagle-import") (part "R-EU_R0603"))
    )
    (comp (ref "R35")
      (value "5k")
      (footprint "eagle-import:R0603")
      (libsource (lib "eagle-import") (part "R-EU_R0603"))
    )
    (comp (ref "R36")
      (value "R-EU_R0603")
      (footprint "eagle-import:R0603")
      (libsource (lib "eagle-import") (part "R-EU_R0603"))
    )
    (comp (ref "R37")
      (value "10k")
      (footprint "eagle-import:R0603")
      (libsource (lib "eagle-import") (part "R-EU_R0603"))
    )
    (comp (ref "R38")
      (value "0R")
      (footprint "eagle-import:R0603")
      (libsource (lib "eagle-import") (part "R-EU_R0603"))
    )
    (comp (ref "R39")
      (value "200R")
      (footprint "eagle-import:R0603")
      (libsource (lib "eagle-import") (part "R-EU_R0603"))
    )
    (comp (ref "R40")
      (value "330k")
      (footprint "eagle-import:R0603")
      (libsource (lib "eagle-import") (part "R-EU_R0603"))
    )
    (comp (ref "R41")
      (value "45.3k")
      (footprint "eagle-import:R0603")
      (libsource (lib "eagle-import") (part "R-EU_R0603"))
    )
    (comp (ref "R42")
      (value "10k 0.1")
      (footprint "eagle-import:R0603")
      (libsource (lib "eagle-import") (part "R-EU_R0603"))
    )
    (comp (ref "R43")
      (value "1.37k 0.1")
      (footprint "eagle-import:R0603")
      (libsource (lib "eagle-import") (part "R-EU_R0603"))
    )
    (comp (ref "R44")
      (value "37k4")
      (footprint "eagle-import:R0603")
      (libsource (lib "eagle-import") (part "R-EU_R0603"))
    )
    (comp (ref "R45")
      (value "500R")
      (footprint "eagle-import:R0603")
      (libsource (lib "eagle-import") (part "R-EU_R0603"))
    )
    (comp (ref "R46")
      (value "5k")
      (footprint "eagle-import:R0603")
      (libsource (lib "eagle-import") (part "R-EU_R0603"))
    )
    (comp (ref "R47")
      (value "R-EU_R0603")
      (footprint "eagle-import:R0603")
      (libsource (lib "eagle-import") (part "R-EU_R0603"))
    )
    (comp (ref "R48")
      (value "10k")
      (footprint "eagle-import:R0603")
      (libsource (lib "eagle-import") (part "R-EU_R0603"))
    )
    (comp (ref "R49")
      (value "0R")
      (footprint "eagle-import:R0603")
      (libsource (lib "eagle-import") (part "R-EU_R0603"))
    )
    (comp (ref "R50")
      (value "200R")
      (footprint "eagle-import:R0603")
      (libsource (lib "eagle-import") (part "R-EU_R0603"))
    )
    (comp (ref "R51")
      (value "330k")
      (footprint "eagle-import:R0603")
      (libsource (lib "eagle-import") (part "R-EU_R0603"))
    )
    (comp (ref "R52")
      (value "45.3k")
      (footprint "eagle-import:R0603")
      (libsource (lib "eagle-import") (part "R-EU_R0603"))
    )
    (comp (ref "R53")
      (value "10k 0.1")
      (footprint "eagle-import:R0603")
      (libsource (lib "eagle-import") (part "R-EU_R0603"))
    )
    (comp (ref "R54")
      (value "1.37k 0.1")
      (footprint "eagle-import:R0603")
      (libsource (lib "eagle-import") (part "R-EU_R0603"))
    )
    (comp (ref "R55")
      (value "37k4")
      (footprint "eagle-import:R0603")
      (libsource (lib "eagle-import") (part "R-EU_R0603"))
    )
    (comp (ref "R56")
      (value "500R")
      (footprint "eagle-import:R0603")
      (libsource (lib "eagle-import") (part "R-EU_R0603"))
    )
    (comp (ref "R57")
      (value "5k")
      (footprint "eagle-import:R0603")
      (libsource (lib "eagle-import") (part "R-EU_R0603"))
    )
    (comp (ref "R58")
      (value "R-EU_R0603")
      (footprint "eagle-import:R0603")
      (libsource (lib "eagle-import") (part "R-EU_R0603"))
    )
    (comp (ref "R59")
      (value "10k")
      (footprint "eagle-import:R0603")
      (libsource (lib "eagle-import") (part "R-EU_R0603"))
    )
    (comp (ref "R60")
      (value "0R")
      (footprint "eagle-import:R0603")
      (libsource (lib "eagle-import") (part "R-EU_R0603"))
    )
    (comp (ref "R61")
      (value "200R")
      (footprint "eagle-import:R0603")
      (libsource (lib "eagle-import") (part "R-EU_R0603"))
    )
    (comp (ref "R62")
      (value "330k")
      (footprint "eagle-import:R0603")
      (libsource (lib "eagle-import") (part "R-EU_R0603"))
    )
    (comp (ref "R63")
      (value "45.3k")
      (footprint "eagle-import:R0603")
      (libsource (lib "eagle-import") (part "R-EU_R0603"))
    )
    (comp (ref "R64")
      (value "10k 0.1")
      (footprint "eagle-import:R0603")
      (libsource (lib "eagle-import") (part "R-EU_R0603"))
    )
    (comp (ref "R65")
      (value "1.37k 0.1")
      (footprint "eagle-import:R0603")
      (libsource (lib "eagle-import") (part "R-EU_R0603"))
    )
    (comp (ref "R66")
      (value "37k4")
      (footprint "eagle-import:R0603")
      (libsource (lib "eagle-import") (part "R-EU_R0603"))
    )
    (comp (ref "R67")
      (value "500R")
      (footprint "eagle-import:R0603")
      (libsource (lib "eagle-import") (part "R-EU_R0603"))
    )
    (comp (ref "R68")
      (value "5k")
      (footprint "eagle-import:R0603")
      (libsource (lib "eagle-import") (part "R-EU_R0603"))
    )
    (comp (ref "R69")
      (value "R-EU_R0603")
      (footprint "eagle-import:R0603")
      (libsource (lib "eagle-import") (part "R-EU_R0603"))
    )
    (comp (ref "R70")
      (value "10k")
      (footprint "eagle-import:R0603")
      (libsource (lib "eagle-import") (part "R-EU_R0603"))
    )
    (comp (ref "R71")
      (value "0R")
      (footprint "eagle-import:R0603")
      (libsource (lib "eagle-import") (part "R-EU_R0603"))
    )
    (comp (ref "R72")
      (value "200R")
      (footprint "eagle-import:R0603")
      (libsource (lib "eagle-import") (part "R-EU_R0603"))
    )
    (comp (ref "R73")
      (value "330k")
      (footprint "eagle-import:R0603")
      (libsource (lib "eagle-import") (part "R-EU_R0603"))
    )
    (comp (ref "R74")
      (value "45.3k")
      (footprint "eagle-import:R0603")
      (libsource (lib "eagle-import") (part "R-EU_R0603"))
    )
    (comp (ref "R75")
      (value "10k 0.1")
      (footprint "eagle-import:R0603")
      (libsource (lib "eagle-import") (part "R-EU_R0603"))
    )
    (comp (ref "R76")
      (value "1.37k 0.1")
      (footprint "eagle-import:R0603")
      (libsource (lib "eagle-import") (part "R-EU_R0603"))
    )
    (comp (ref "R77")
      (value "37k4")
      (footprint "eagle-import:R0603")
      (libsource (lib "eagle-import") (part "R-EU_R0603"))
    )
    (comp (ref "R78")
      (value "500R")
      (footprint "eagle-import:R0603")
      (libsource (lib "eagle-import") (part "R-EU_R0603"))
    )
    (comp (ref "R79")
      (value "5k")
      (footprint "eagle-import:R0603")
      (libsource (lib "eagle-import") (part "R-EU_R0603"))
    )
    (comp (ref "R80")
      (value "R-EU_R0603")
      (footprint "eagle-import:R0603")
      (libsource (lib "eagle-import") (part "R-EU_R0603"))
    )
    (comp (ref "R81")
      (value "10k")
      (footprint "eagle-import:R0603")
      (libsource (lib "eagle-import") (part "R-EU_R0603"))
    )
    (comp (ref "R82")
      (value "0R")
      (footprint "eagle-import:R0603")
      (libsource (lib "eagle-import") (part "R-EU_R0603"))
    )
    (comp (ref "R83")
      (value "200R")
      (footprint "eagle-import:R0603")
      (libsource (lib "eagle-import") (part "R-EU_R0603"))
    )
    (comp (ref "R84")
      (value "10k 0.1")
      (footprint "eagle-import:R0603")
      (libsource (lib "eagle-import") (part "R-EU_R0603"))
    )
    (comp (ref "R85")
      (value "1.37k 0.1")
      (footprint "eagle-import:R0603")
      (libsource (lib "eagle-import") (part "R-EU_R0603"))
    )
    (comp (ref "R86")
      (value "37k4")
      (footprint "eagle-import:R0603")
      (libsource (lib "eagle-import") (part "R-EU_R0603"))
    )
    (comp (ref "R87")
      (value "500R")
      (footprint "eagle-import:R0603")
      (libsource (lib "eagle-import") (part "R-EU_R0603"))
    )
    (comp (ref "R88")
      (value "5k")
      (footprint "eagle-import:R0603")
      (libsource (lib "eagle-import") (part "R-EU_R0603"))
    )
    (comp (ref "R89")
      (value "R-EU_R0603")
      (footprint "eagle-import:R0603")
      (libsource (lib "eagle-import") (part "R-EU_R0603"))
    )
    (comp (ref "R90")
      (value "10k")
      (footprint "eagle-import:R0603")
      (libsource (lib "eagle-import") (part "R-EU_R0603"))
    )
    (comp (ref "R91")
      (value "0R")
      (footprint "eagle-import:R0603")
      (libsource (lib "eagle-import") (part "R-EU_R0603"))
    )
    (comp (ref "R92")
      (value "200R")
      (footprint "eagle-import:R0603")
      (libsource (lib "eagle-import") (part "R-EU_R0603"))
    )
    (comp (ref "U$6")
      (value "TPS3852")
      (footprint "eagle-import:SON65P300X300X100-9N")
      (libsource (lib "eagle-import") (part "TPS3852"))
    )
    (comp (ref "U$7")
      (value "TPS3852")
      (footprint "eagle-import:SON65P300X300X100-9N")
      (libsource (lib "eagle-import") (part "TPS3852"))
    )
    (comp (ref "U$8")
      (value "TPS3852")
      (footprint "eagle-import:SON65P300X300X100-9N")
      (libsource (lib "eagle-import") (part "TPS3852"))
    )
    (comp (ref "U$9")
      (value "TPS3852")
      (footprint "eagle-import:SON65P300X300X100-9N")
      (libsource (lib "eagle-import") (part "TPS3852"))
    )
    (comp (ref "U$10")
      (value "TPS3852")
      (footprint "eagle-import:SON65P300X300X100-9N")
      (libsource (lib "eagle-import") (part "TPS3852"))
    )
    (comp (ref "U$11")
      (value "TPS3852")
      (footprint "eagle-import:SON65P300X300X100-9N")
      (libsource (lib "eagle-import") (part "TPS3852"))
    )
    (comp (ref "U$12")
      (value "TPS3852")
      (footprint "eagle-import:SON65P300X300X100-9N")
      (libsource (lib "eagle-import") (part "TPS3852"))
    )
    (comp (ref "U2")
      (value "TPS54531DDA_3D")
      (footprint "eagle-import:SOIC127P600X150-9T240X310")
      (libsource (lib "eagle-import") (part "TPS54531DDA_3D"))
    )
    (comp (ref "U3")
      (value "TPS54531DDA_3D")
      (footprint "eagle-import:SOIC127P600X150-9T240X310")
      (libsource (lib "eagle-import") (part "TPS54531DDA_3D"))
    )
    (comp (ref "U4")
      (value "TPS54531DDA_3D")
      (footprint "eagle-import:SOIC127P600X150-9T240X310")
      (libsource (lib "eagle-import") (part "TPS54531DDA_3D"))
    )
    (comp (ref "U5")
      (value "TPS54531DDA_3D")
      (footprint "eagle-import:SOIC127P600X150-9T240X310")
      (libsource (lib "eagle-import") (part "TPS54531DDA_3D"))
    )
    (comp (ref "U6")
      (value "TPS54531DDA_3D")
      (footprint "eagle-import:SOIC127P600X150-9T240X310")
      (libsource (lib "eagle-import") (part "TPS54531DDA_3D"))
    )
    (comp (ref "U7")
      (value "TPS54531DDA_3D")
      (footprint "eagle-import:SOIC127P600X150-9T240X310")
      (libsource (lib "eagle-import") (part "TPS54531DDA_3D"))
    )
    (comp (ref "U8")
      (value "TPS54531DDA_3D")
      (footprint "eagle-import:SOIC127P600X150-9T240X310")
      (libsource (lib "eagle-import") (part "TPS54531DDA_3D"))
    )
  )
  (nets
    (net (code "1") (name "+3V3") (class "Default")
      (node (ref "C105") (pin "1") (pinfunction "1_1") (pintype "passive"))
      (node (ref "C120") (pin "1") (pinfunction "1_1") (pintype "passive"))
      (node (ref "C26") (pin "1") (pinfunction "1_1") (pintype "passive"))
      (node (ref "C45") (pin "1") (pinfunction "1_1") (pintype "passive"))
      (node (ref "C60") (pin "1") (pinfunction "1_1") (pintype "passive"))
      (node (ref "C75") (pin "1") (pinfunction "1_1") (pintype "passive"))
      (node (ref "C90") (pin "1") (pinfunction "1_1") (pintype "passive"))
      (node (ref "R24") (pin "2") (pinfunction "2_2") (pintype "passive"))
      (node (ref "R25") (pin "1") (pinfunction "1_1") (pintype "passive"))
      (node (ref "R26") (pin "2") (pinfunction "2_2") (pintype "passive"))
      (node (ref "R27") (pin "2") (pinfunction "2_2") (pintype "passive"))
      (node (ref "R35") (pin "2") (pinfunction "2_2") (pintype "passive"))
      (node (ref "R36") (pin "1") (pinfunction "1_1") (pintype "passive"))
      (node (ref "R37") (pin "2") (pinfunction "2_2") (pintype "passive"))
      (node (ref "R38") (pin "2") (pinfunction "2_2") (pintype "passive"))
      (node (ref "R46") (pin "2") (pinfunction "2_2") (pintype "passive"))
      (node (ref "R47") (pin "1") (pinfunction "1_1") (pintype "passive"))
      (node (ref "R48") (pin "2") (pinfunction "2_2") (pintype "passive"))
      (node (ref "R49") (pin "2") (pinfunction "2_2") (pintype "passive"))
      (node (ref "R57") (pin "2") (pinfunction "2_2") (pintype "passive"))
      (node (ref "R58") (pin "1") (pinfunction "1_1") (pintype "passive"))
      (node (ref "R59") (pin "2") (pinfunction "2_2") (pintype "passive"))
      (node (ref "R60") (pin "2") (pinfunction "2_2") (pintype "passive"))
      (node (ref "R68") (pin "2") (pinfunction "2_2") (pintype "passive"))
      (node (ref "R69") (pin "1") (pinfunction "1_1") (pintype "passive"))
      (node (ref "R70") (pin "2") (pinfunction "2_2") (pintype "passive"))
      (node (ref "R71") (pin "2") (pinfunction "2_2") (pintype "passive"))
      (node (ref "R79") (pin "2") (pinfunction "2_2") (pintype "passive"))
      (node (ref "R80") (pin "1") (pinfunction "1_1") (pintype "passive"))
      (node (ref "R81") (pin "2") (pinfunction "2_2") (pintype "passive"))
      (node (ref "R82") (pin "2") (pinfunction "2_2") (pintype "passive"))
      (node (ref "R88") (pin "2") (pinfunction "2_2") (pintype "passive"))
      (node (ref "R89") (pin "1") (pinfunction "1_1") (pintype "passive"))
      (node (ref "R90") (pin "2") (pinfunction "2_2") (pintype "passive"))
      (node (ref "R91") (pin "2") (pinfunction "2_2") (pintype "passive"))
      (node (ref "U$10") (pin "1") (pinfunction "VDD_1") (pintype "bidirectional"))
      (node (ref "U$11") (pin "1") (pinfunction "VDD_1") (pintype "bidirectional"))
      (node (ref "U$12") (pin "1") (pinfunction "VDD_1") (pintype "bidirectional"))
      (node (ref "U$5") (pin "19") (pinfunction "19_19") (pintype "bidirectional"))
      (node (ref "U$6") (pin "1") (pinfunction "VDD_1") (pintype "bidirectional"))
      (node (ref "U$7") (pin "1") (pinfunction "VDD_1") (pintype "bidirectional"))
      (node (ref "U$8") (pin "1") (pinfunction "VDD_1") (pintype "bidirectional"))
      (node (ref "U$9") (pin "1") (pinfunction "VDD_1") (pintype "bidirectional"))
    )
    (net (code "2") (name "+11") (class "Default")
      (node (ref "U$13") (pin "14") (pinfunction "14_14") (pintype "bidirectional"))
      (node (ref "U$14") (pin "13") (pinfunction "13_13") (pintype "bidirectional"))
    )
    (net (code "3") (name "3V8") (class "Default")
      (node (ref "C19") (pin "1") (pinfunction "+_1") (pintype "passive"))
      (node (ref "C20") (pin "1") (pinfunction "1_1") (pintype "passive"))
      (node (ref "C21") (pin "1") (pinfunction "1_1") (pintype "passive"))
      (node (ref "C22") (pin "1") (pinfunction "1_1") (pintype "passive"))
      (node (ref "L2") (pin "2") (pinfunction "2_2") (pintype "passive"))
      (node (ref "R14") (pin "2") (pinfunction "2_2") (pintype "passive"))
      (node (ref "R2") (pin "2") (pinfunction "2_2") (pintype "passive"))
      (node (ref "U$3") (pin "2") (pinfunction "2_2") (pintype "bidirectional"))
      (node (ref "U$3") (pin "4") (pinfunction "4_4") (pintype "bidirectional"))
      (node (ref "U$4") (pin "1") (pinfunction "1_1") (pintype "bidirectional"))
      (node (ref "U$4") (pin "3") (pinfunction "3_3") (pintype "bidirectional"))
    )
    (net (code "4") (name "3V8'") (class "Default")
      (node (ref "C83") (pin "1") (pinfunction "+_1") (pintype "passive"))
      (node (ref "C84") (pin "1") (pinfunction "1_1") (pintype "passive"))
      (node (ref "C85") (pin "1") (pinfunction "1_1") (pintype "passive"))
      (node (ref "C86") (pin "1") (pinfunction "1_1") (pintype "passive"))
      (node (ref "L6") (pin "2") (pinfunction "2_2") (pintype "passive"))
      (node (ref "R4") (pin "2") (pinfunction "2_2") (pintype "passive"))
      (node (ref "R64") (pin "2") (pinfunction "2_2") (pintype "passive"))
      (node (ref "U$1") (pin "5") (pinfunction "5_5") (pintype "bidirectional"))
      (node (ref "U$1") (pin "6") (pinfunction "6_6") (pintype "bidirectional"))
      (node (ref "U$2") (pin "5") (pinfunction "5_5") (pintype "bidirectional"))
      (node (ref "U$2") (pin "6") (pinfunction "6_6") (pintype "bidirectional"))
    )
    (net (code "5") (name "5V5") (class "Default")
      (node (ref "C38") (pin "1") (pinfunction "+_1") (pintype "passive"))
      (node (ref "C39") (pin "1") (pinfunction "1_1") (pintype "passive"))
      (node (ref "C40") (pin "1") (pinfunction "1_1") (pintype "passive"))
      (node (ref "C41") (pin "1") (pinfunction "1_1") (pintype "passive"))
      (node (ref "L3") (pin "2") (pinfunction "2_2") (pintype "passive"))
      (node (ref "R3") (pin "2") (pinfunction "2_2") (pintype "passive"))
      (node (ref "R31") (pin "2") (pinfunction "2_2") (pintype "passive"))
      (node (ref "U$3") (pin "10") (pinfunction "10_10") (pintype "bidirectional"))
      (node (ref "U$3") (pin "9") (pinfunction "9_9") (pintype "bidirectional"))
      (node (ref "U$4") (pin "10") (pinfunction "10_10") (pintype "bidirectional"))
      (node (ref "U$4") (pin "9") (pinfunction "9_9") (pintype "bidirectional"))
    )
    (net (code "6") (name "5V5'") (class "Default")
      (node (ref "C68") (pin "1") (pinfunction "+_1") (pintype "passive"))
      (node (ref "C69") (pin "1") (pinfunction "1_1") (pintype "passive"))
      (node (ref "C70") (pin "1") (pinfunction "1_1") (pintype "passive"))
      (node (ref "C71") (pin "1") (pinfunction "1_1") (pintype "passive"))
      (node (ref "L5") (pin "2") (pinfunction "2_2") (pintype "passive"))
      (node (ref "R53") (pin "2") (pinfunction "2_2") (pintype "passive"))
      (node (ref "R6") (pin "2") (pinfunction "2_2") (pintype "passive"))
      (node (ref "U$1") (pin "15") (pinfunction "15_15") (pintype "bidirectional"))
      (node (ref "U$1") (pin "16") (pinfunction "16_16") (pintype "bidirectional"))
      (node (ref "U$2") (pin "15") (pinfunction "15_15") (pintype "bidirectional"))
      (node (ref "U$2") (pin "16") (pinfunction "16_16") (pintype "bidirectional"))
    )
    (net (code "7") (name "6V6") (class "Default")
      (node (ref "C53") (pin "1") (pinfunction "+_1") (pintype "passive"))
      (node (ref "C54") (pin "1") (pinfunction "1_1") (pintype "passive"))
      (node (ref "C55") (pin "1") (pinfunction "1_1") (pintype "passive"))
      (node (ref "C56") (pin "1") (pinfunction "1_1") (pintype "passive"))
      (node (ref "L4") (pin "2") (pinfunction "2_2") (pintype "passive"))
      (node (ref "R42") (pin "2") (pinfunction "2_2") (pintype "passive"))
      (node (ref "R7") (pin "2") (pinfunction "2_2") (pintype "passive"))
      (node (ref "U$3") (pin "13") (pinfunction "13_13") (pintype "bidirectional"))
      (node (ref "U$3") (pin "14") (pinfunction "14_14") (pintype "bidirectional"))
      (node (ref "U$4") (pin "13") (pinfunction "13_13") (pintype "bidirectional"))
      (node (ref "U$4") (pin "14") (pinfunction "14_14") (pintype "bidirectional"))
    )
    (net (code "8") (name "7V4") (class "Default")
      (node (ref "C100") (pin "1") (pinfunction "1_1") (pintype "passive"))
      (node (ref "C101") (pin "1") (pinfunction "1_1") (pintype "passive"))
      (node (ref "C98") (pin "1") (pinfunction "+_1") (pintype "passive"))
      (node (ref "C99") (pin "1") (pinfunction "1_1") (pintype "passive"))
      (node (ref "L7") (pin "2") (pinfunction "2_2") (pintype "passive"))
      (node (ref "R5") (pin "2") (pinfunction "2_2") (pintype "passive"))
      (node (ref "R75") (pin "2") (pinfunction "2_2") (pintype "passive"))
      (node (ref "U$3") (pin "1") (pinfunction "1_1") (pintype "bidirectional"))
      (node (ref "U$3") (pin "3") (pinfunction "3_3") (pintype "bidirectional"))
      (node (ref "U$4") (pin "2") (pinfunction "2_2") (pintype "bidirectional"))
      (node (ref "U$4") (pin "4") (pinfunction "4_4") (pintype "bidirectional"))
    )
    (net (code "9") (name "13V") (class "Default")
      (node (ref "C113") (pin "1") (pinfunction "+_1") (pintype "passive"))
      (node (ref "C114") (pin "1") (pinfunction "1_1") (pintype "passive"))
      (node (ref "C115") (pin "1") (pinfunction "1_1") (pintype "passive"))
      (node (ref "C116") (pin "1") (pinfunction "1_1") (pintype "passive"))
      (node (ref "L8") (pin "2") (pinfunction "2_2") (pintype "passive"))
      (node (ref "R1") (pin "2") (pinfunction "2_2") (pintype "passive"))
      (node (ref "R84") (pin "2") (pinfunction "2_2") (pintype "passive"))
      (node (ref "U$1") (pin "18") (pinfunction "18_18") (pintype "bidirectional"))
      (node (ref "U$1") (pin "20") (pinfunction "20_20") (pintype "bidirectional"))
      (node (ref "U$2") (pin "17") (pinfunction "17_17") (pintype "bidirectional"))
      (node (ref "U$2") (pin "19") (pinfunction "19_19") (pintype "bidirectional"))
    )
    (net (code "10") (name "AGND") (class "Default")
      (node (ref "U$13") (pin "6") (pinfunction "6_6") (pintype "bidirectional"))
      (node (ref "U$14") (pin "5") (pinfunction "5_5") (pintype "bidirectional"))
    )
    (net (code "11") (name "BURNOUT+") (class "Default")
      (node (ref "U$13") (pin "10") (pinfunction "10_10") (pintype "bidirectional"))
      (node (ref "U$14") (pin "9") (pinfunction "9_9") (pintype "bidirectional"))
    )
    (net (code "12") (name "BURNOUT-") (class "Default")
      (node (ref "U$13") (pin "8") (pinfunction "8_8") (pintype "bidirectional"))
      (node (ref "U$14") (pin "7") (pinfunction "7_7") (pintype "bidirectional"))
    )
    (net (code "13") (name "CAN2H") (class "Default")
      (node (ref "U$3") (pin "15") (pinfunction "15_15") (pintype "bidirectional"))
      (node (ref "U$4") (pin "16") (pinfunction "16_16") (pintype "bidirectional"))
    )
    (net (code "14") (name "CAN2L") (class "Default")
      (node (ref "U$3") (pin "16") (pinfunction "16_16") (pintype "bidirectional"))
      (node (ref "U$4") (pin "15") (pinfunction "15_15") (pintype "bidirectional"))
    )
    (net (code "15") (name "CANH") (class "Default")
      (node (ref "U$1") (pin "1") (pinfunction "1_1") (pintype "bidirectional"))
      (node (ref "U$2") (pin "2") (pinfunction "2_2") (pintype "bidirectional"))
    )
    (net (code "16") (name "CANL") (class "Default")
      (node (ref "U$1") (pin "3") (pinfunction "3_3") (pintype "bidirectional"))
      (node (ref "U$2") (pin "4") (pinfunction "4_4") (pintype "bidirectional"))
    )
    (net (code "17") (name "FREE1") (class "Default")
      (node (ref "U$1") (pin "12") (pinfunction "12_12") (pintype "bidirectional"))
      (node (ref "U$2") (pin "11") (pinfunction "11_11") (pintype "bidirectional"))
    )
    (net (code "18") (name "FREE2") (class "Default")
      (node (ref "U$3") (pin "6") (pinfunction "6_6") (pintype "bidirectional"))
      (node (ref "U$4") (pin "5") (pinfunction "5_5") (pintype "bidirectional"))
    )
    (net (code "19") (name "GND") (class "Default")
      (node (ref "C1") (pin "2") (pinfunction "2_2") (pintype "passive"))
      (node (ref "C10") (pin "2") (pinfunction "2_2") (pintype "passive"))
      (node (ref "C100") (pin "2") (pinfunction "2_2") (pintype "passive"))
      (node (ref "C101") (pin "2") (pinfunction "2_2") (pintype "passive"))
      (node (ref "C102") (pin "2") (pinfunction "2_2") (pintype "passive"))
      (node (ref "C103") (pin "2") (pinfunction "2_2") (pintype "passive"))
      (node (ref "C104") (pin "2") (pinfunction "2_2") (pintype "passive"))
      (node (ref "C105") (pin "2") (pinfunction "2_2") (pintype "passive"))
      (node (ref "C106") (pin "2") (pinfunction "2_2") (pintype "passive"))
      (node (ref "C107") (pin "2") (pinfunction "2_2") (pintype "passive"))
      (node (ref "C108") (pin "2") (pinfunction "2_2") (pintype "passive"))
      (node (ref "C109") (pin "2") (pinfunction "2_2") (pintype "passive"))
      (node (ref "C111") (pin "2") (pinfunction "2_2") (pintype "passive"))
      (node (ref "C113") (pin "2") (pinfunction "-_2") (pintype "passive"))
      (node (ref "C114") (pin "2") (pinfunction "2_2") (pintype "passive"))
      (node (ref "C115") (pin "2") (pinfunction "2_2") (pintype "passive"))
      (node (ref "C116") (pin "2") (pinfunction "2_2") (pintype "passive"))
      (node (ref "C117") (pin "2") (pinfunction "2_2") (pintype "passive"))
      (node (ref "C118") (pin "2") (pinfunction "2_2") (pintype "passive"))
      (node (ref "C119") (pin "2") (pinfunction "2_2") (pintype "passive"))
      (node (ref "C120") (pin "2") (pinfunction "2_2") (pintype "passive"))
      (node (ref "C13") (pin "2") (pinfunction "2_2") (pintype "passive"))
      (node (ref "C14") (pin "2") (pinfunction "2_2") (pintype "passive"))
      (node (ref "C15") (pin "2") (pinfunction "2_2") (pintype "passive"))
      (node (ref "C17") (pin "2") (pinfunction "2_2") (pintype "passive"))
      (node (ref "C19") (pin "2") (pinfunction "-_2") (pintype "passive"))
      (node (ref "C2") (pin "2") (pinfunction "-_2") (pintype "passive"))
      (node (ref "C20") (pin "2") (pinfunction "2_2") (pintype "passive"))
      (node (ref "C21") (pin "2") (pinfunction "2_2") (pintype "passive"))
      (node (ref "C22") (pin "2") (pinfunction "2_2") (pintype "passive"))
      (node (ref "C23") (pin "2") (pinfunction "2_2") (pintype "passive"))
      (node (ref "C24") (pin "2") (pinfunction "2_2") (pintype "passive"))
      (node (ref "C25") (pin "2") (pinfunction "2_2") (pintype "passive"))
      (node (ref "C26") (pin "2") (pinfunction "2_2") (pintype "passive"))
      (node (ref "C3") (pin "2") (pinfunction "-_2") (pintype "passive"))
      (node (ref "C31") (pin "2") (pinfunction "2_2") (pintype "passive"))
      (node (ref "C32") (pin "2") (pinfunction "2_2") (pintype "passive"))
      (node (ref "C33") (pin "2") (pinfunction "2_2") (pintype "passive"))
      (node (ref "C34") (pin "2") (pinfunction "2_2") (pintype "passive"))
      (node (ref "C36") (pin "2") (pinfunction "2_2") (pintype "passive"))
      (node (ref "C38") (pin "2") (pinfunction "-_2") (pintype "passive"))
      (node (ref "C39") (pin "2") (pinfunction "2_2") (pintype "passive"))
      (node (ref "C4") (pin "2") (pinfunction "2_2") (pintype "passive"))
      (node (ref "C40") (pin "2") (pinfunction "2_2") (pintype "passive"))
      (node (ref "C41") (pin "2") (pinfunction "2_2") (pintype "passive"))
      (node (ref "C42") (pin "2") (pinfunction "2_2") (pintype "passive"))
      (node (ref "C43") (pin "2") (pinfunction "2_2") (pintype "passive"))
      (node (ref "C44") (pin "2") (pinfunction "2_2") (pintype "passive"))
      (node (ref "C45") (pin "2") (pinfunction "2_2") (pintype "passive"))
      (node (ref "C46") (pin "2") (pinfunction "2_2") (pintype "passive"))
      (node (ref "C47") (pin "2") (pinfunction "2_2") (pintype "passive"))
      (node (ref "C48") (pin "2") (pinfunction "2_2") (pintype "passive"))
      (node (ref "C49") (pin "2") (pinfunction "2_2") (pintype "passive"))
      (node (ref "C5") (pin "2") (pinfunction "2_2") (pintype "passive"))
      (node (ref "C51") (pin "2") (pinfunction "2_2") (pintype "passive"))
      (node (ref "C53") (pin "2") (pinfunction "-_2") (pintype "passive"))
      (node (ref "C54") (pin "2") (pinfunction "2_2") (pintype "passive"))
      (node (ref "C55") (pin "2") (pinfunction "2_2") (pintype "passive"))
      (node (ref "C56") (pin "2") (pinfunction "2_2") (pintype "passive"))
      (node (ref "C57") (pin "2") (pinfunction "2_2") (pintype "passive"))
      (node (ref "C58") (pin "2") (pinfunction "2_2") (pintype "passive"))
      (node (ref "C59") (pin "2") (pinfunction "2_2") (pintype "passive"))
      (node (ref "C6") (pin "2") (pinfunction "2_2") (pintype "passive"))
      (node (ref "C60") (pin "2") (pinfunction "2_2") (pintype "passive"))
      (node (ref "C61") (pin "2") (pinfunction "2_2") (pintype "passive"))
      (node (ref "C62") (pin "2") (pinfunction "2_2") (pintype "passive"))
      (node (ref "C63") (pin "2") (pinfunction "2_2") (pintype "passive"))
      (node (ref "C64") (pin "2") (pinfunction "2_2") (pintype "passive"))
      (node (ref "C66") (pin "2") (pinfunction "2_2") (pintype "passive"))
      (node (ref "C68") (pin "2") (pinfunction "-_2") (pintype "passive"))
      (node (ref "C69") (pin "2") (pinfunction "2_2") (pintype "passive"))
      (node (ref "C7") (pin "2") (pinfunction "2_2") (pintype "passive"))
      (node (ref "C70") (pin "2") (pinfunction "2_2") (pintype "passive"))
      (node (ref "C71") (pin "2") (pinfunction "2_2") (pintype "passive"))
      (node (ref "C72") (pin "2") (pinfunction "2_2") (pintype "passive"))
      (node (ref "C73") (pin "2") (pinfunction "2_2") (pintype "passive"))
      (node (ref "C74") (pin "2") (pinfunction "2_2") (pintype "passive"))
      (node (ref "C75") (pin "2") (pinfunction "2_2") (pintype "passive"))
      (node (ref "C76") (pin "2") (pinfunction "2_2") (pintype "passive"))
      (node (ref "C77") (pin "2") (pinfunction "2_2") (pintype "passive"))
      (node (ref "C78") (pin "2") (pinfunction "2_2") (pintype "passive"))
      (node (ref "C79") (pin "2") (pinfunction "2_2") (pintype "passive"))
      (node (ref "C8") (pin "2") (pinfunction "2_2") (pintype "passive"))
      (node (ref "C81") (pin "2") (pinfunction "2_2") (pintype "passive"))
      (node (ref "C83") (pin "2") (pinfunction "-_2") (pintype "passive"))
      (node (ref "C84") (pin "2") (pinfunction "2_2") (pintype "passive"))
      (node (ref "C85") (pin "2") (pinfunction "2_2") (pintype "passive"))
      (node (ref "C86") (pin "2") (pinfunction "2_2") (pintype "passive"))
      (node (ref "C87") (pin "2") (pinfunction "2_2") (pintype "passive"))
      (node (ref "C88") (pin "2") (pinfunction "2_2") (pintype "passive"))
      (node (ref "C89") (pin "2") (pinfunction "2_2") (pintype "passive"))
      (node (ref "C9") (pin "2") (pinfunction "2_2") (pintype "passive"))
      (node (ref "C90") (pin "2") (pinfunction "2_2") (pintype "passive"))
      (node (ref "C91") (pin "2") (pinfunction "2_2") (pintype "passive"))
      (node (ref "C92") (pin "2") (pinfunction "2_2") (pintype "passive"))
      (node (ref "C93") (pin "2") (pinfunction "2_2") (pintype "passive"))
      (node (ref "C94") (pin "2") (pinfunction "2_2") (pintype "passive"))
      (node (ref "C96") (pin "2") (pinfunction "2_2") (pintype "passive"))
      (node (ref "C98") (pin "2") (pinfunction "-_2") (pintype "passive"))
      (node (ref "C99") (pin "2") (pinfunction "2_2") (pintype "passive"))
      (node (ref "D2") (pin "A") (pinfunction "A_A") (pintype "passive"))
      (node (ref "D3") (pin "A") (pinfunction "A_A") (pintype "passive"))
      (node (ref "D4") (pin "A") (pinfunction "A_A") (pintype "passive"))
      (node (ref "D5") (pin "A") (pinfunction "A_A") (pintype "passive"))
      (node (ref "D6") (pin "A") (pinfunction "A_A") (pintype "passive"))
      (node (ref "D7") (pin "A") (pinfunction "A_A") (pintype "passive"))
      (node (ref "D8") (pin "A") (pinfunction "A_A") (pintype "passive"))
      (node (ref "J3") (pin "2") (pinfunction "2_2") (pintype "bidirectional"))
      (node (ref "J3") (pin "4") (pinfunction "4_4") (pintype "bidirectional"))
      (node (ref "J3") (pin "6") (pinfunction "6_6") (pintype "bidirectional"))
      (node (ref "LED1") (pin "C") (pinfunction "C_C") (pintype "passive"))
      (node (ref "LED2") (pin "C") (pinfunction "C_C") (pintype "passive"))
      (node (ref "LED3") (pin "C") (pinfunction "C_C") (pintype "passive"))
      (node (ref "LED4") (pin "C") (pinfunction "C_C") (pintype "passive"))
      (node (ref "LED5") (pin "C") (pinfunction "C_C") (pintype "passive"))
      (node (ref "LED6") (pin "C") (pinfunction "C_C") (pintype "passive"))
      (node (ref "LED7") (pin "C") (pinfunction "C_C") (pintype "passive"))
      (node (ref "Q1") (pin "2") (pinfunction "S_2") (pintype "passive"))
      (node (ref "Q11") (pin "2") (pinfunction "S_2") (pintype "passive"))
      (node (ref "Q13") (pin "2") (pinfunction "S_2") (pintype "passive"))
      (node (ref "Q15") (pin "2") (pinfunction "S_2") (pintype "passive"))
      (node (ref "Q5") (pin "2") (pinfunction "S_2") (pintype "passive"))
      (node (ref "Q7") (pin "2") (pinfunction "S_2") (pintype "passive"))
      (node (ref "Q9") (pin "2") (pinfunction "S_2") (pintype "passive"))
      (node (ref "R11") (pin "1") (pinfunction "1_1") (pintype "passive"))
      (node (ref "R13") (pin "1") (pinfunction "1_1") (pintype "passive"))
      (node (ref "R17") (pin "1") (pinfunction "1_1") (pintype "passive"))
      (node (ref "R18") (pin "2") (pinfunction "2_2") (pintype "passive"))
      (node (ref "R30") (pin "1") (pinfunction "1_1") (pintype "passive"))
      (node (ref "R32") (pin "1") (pinfunction "1_1") (pintype "passive"))
      (node (ref "R33") (pin "2") (pinfunction "2_2") (pintype "passive"))
      (node (ref "R41") (pin "1") (pinfunction "1_1") (pintype "passive"))
      (node (ref "R43") (pin "1") (pinfunction "1_1") (pintype "passive"))
      (node (ref "R44") (pin "2") (pinfunction "2_2") (pintype "passive"))
      (node (ref "R52") (pin "1") (pinfunction "1_1") (pintype "passive"))
      (node (ref "R54") (pin "1") (pinfunction "1_1") (pintype "passive"))
      (node (ref "R55") (pin "2") (pinfunction "2_2") (pintype "passive"))
      (node (ref "R63") (pin "1") (pinfunction "1_1") (pintype "passive"))
      (node (ref "R65") (pin "1") (pinfunction "1_1") (pintype "passive"))
      (node (ref "R66") (pin "2") (pinfunction "2_2") (pintype "passive"))
      (node (ref "R74") (pin "1") (pinfunction "1_1") (pintype "passive"))
      (node (ref "R76") (pin "1") (pinfunction "1_1") (pintype "passive"))
      (node (ref "R77") (pin "2") (pinfunction "2_2") (pintype "passive"))
      (node (ref "R85") (pin "1") (pinfunction "1_1") (pintype "passive"))
      (node (ref "R86") (pin "2") (pinfunction "2_2") (pintype "passive"))
      (node (ref "U$1") (pin "14") (pinfunction "14_14") (pintype "bidirectional"))
      (node (ref "U$1") (pin "2") (pinfunction "2_2") (pintype "bidirectional"))
      (node (ref "U$1") (pin "4") (pinfunction "4_4") (pintype "bidirectional"))
      (node (ref "U$10") (pin "4") (pinfunction "GND_4") (pintype "bidirectional"))
      (node (ref "U$10") (pin "9") (pinfunction "TP_9") (pintype "bidirectional"))
      (node (ref "U$10") (pin "9_1") (pinfunction "TP_9_1") (pintype "bidirectional"))
      (node (ref "U$10") (pin "9_2") (pinfunction "TP_9_2") (pintype "bidirectional"))
      (node (ref "U$10") (pin "9_3") (pinfunction "TP_9_3") (pintype "bidirectional"))
      (node (ref "U$10") (pin "9_4") (pinfunction "TP_9_4") (pintype "bidirectional"))
      (node (ref "U$11") (pin "4") (pinfunction "GND_4") (pintype "bidirectional"))
      (node (ref "U$11") (pin "9") (pinfunction "TP_9") (pintype "bidirectional"))
      (node (ref "U$11") (pin "9_1") (pinfunction "TP_9_1") (pintype "bidirectional"))
      (node (ref "U$11") (pin "9_2") (pinfunction "TP_9_2") (pintype "bidirectional"))
      (node (ref "U$11") (pin "9_3") (pinfunction "TP_9_3") (pintype "bidirectional"))
      (node (ref "U$11") (pin "9_4") (pinfunction "TP_9_4") (pintype "bidirectional"))
      (node (ref "U$12") (pin "4") (pinfunction "GND_4") (pintype "bidirectional"))
      (node (ref "U$12") (pin "9") (pinfunction "TP_9") (pintype "bidirectional"))
      (node (ref "U$12") (pin "9_1") (pinfunction "TP_9_1") (pintype "bidirectional"))
      (node (ref "U$12") (pin "9_2") (pinfunction "TP_9_2") (pintype "bidirectional"))
      (node (ref "U$12") (pin "9_3") (pinfunction "TP_9_3") (pintype "bidirectional"))
      (node (ref "U$12") (pin "9_4") (pinfunction "TP_9_4") (pintype "bidirectional"))
      (node (ref "U$2") (pin "1") (pinfunction "1_1") (pintype "bidirectional"))
      (node (ref "U$2") (pin "13") (pinfunction "13_13") (pintype "bidirectional"))
      (node (ref "U$2") (pin "3") (pinfunction "3_3") (pintype "bidirectional"))
      (node (ref "U$3") (pin "17") (pinfunction "17_17") (pintype "bidirectional"))
      (node (ref "U$3") (pin "18") (pinfunction "18_18") (pintype "bidirectional"))
      (node (ref "U$4") (pin "17") (pinfunction "17_17") (pintype "bidirectional"))
      (node (ref "U$4") (pin "18") (pinfunction "18_18") (pintype "bidirectional"))
      (node (ref "U$5") (pin "1") (pinfunction "1_1") (pintype "bidirectional"))
      (node (ref "U$5") (pin "2") (pinfunction "2_2") (pintype "bidirectional"))
      (node (ref "U$5") (pin "3") (pinfunction "3_3") (pintype "bidirectional"))
      (node (ref "U$5") (pin "4") (pinfunction "4_4") (pintype "bidirectional"))
      (node (ref "U$5") (pin "6") (pinfunction "6_6") (pintype "bidirectional"))
      (node (ref "U$6") (pin "4") (pinfunction "GND_4") (pintype "bidirectional"))
      (node (ref "U$6") (pin "9") (pinfunction "TP_9") (pintype "bidirectional"))
      (node (ref "U$6") (pin "9_1") (pinfunction "TP_9_1") (pintype "bidirectional"))
      (node (ref "U$6") (pin "9_2") (pinfunction "TP_9_2") (pintype "bidirectional"))
      (node (ref "U$6") (pin "9_3") (pinfunction "TP_9_3") (pintype "bidirectional"))
      (node (ref "U$6") (pin "9_4") (pinfunction "TP_9_4") (pintype "bidirectional"))
      (node (ref "U$7") (pin "4") (pinfunction "GND_4") (pintype "bidirectional"))
      (node (ref "U$7") (pin "9") (pinfunction "TP_9") (pintype "bidirectional"))
      (node (ref "U$7") (pin "9_1") (pinfunction "TP_9_1") (pintype "bidirectional"))
      (node (ref "U$7") (pin "9_2") (pinfunction "TP_9_2") (pintype "bidirectional"))
      (node (ref "U$7") (pin "9_3") (pinfunction "TP_9_3") (pintype "bidirectional"))
      (node (ref "U$7") (pin "9_4") (pinfunction "TP_9_4") (pintype "bidirectional"))
      (node (ref "U$8") (pin "4") (pinfunction "GND_4") (pintype "bidirectional"))
      (node (ref "U$8") (pin "9") (pinfunction "TP_9") (pintype "bidirectional"))
      (node (ref "U$8") (pin "9_1") (pinfunction "TP_9_1") (pintype "bidirectional"))
      (node (ref "U$8") (pin "9_2") (pinfunction "TP_9_2") (pintype "bidirectional"))
      (node (ref "U$8") (pin "9_3") (pinfunction "TP_9_3") (pintype "bidirectional"))
      (node (ref "U$8") (pin "9_4") (pinfunction "TP_9_4") (pintype "bidirectional"))
      (node (ref "U$9") (pin "4") (pinfunction "GND_4") (pintype "bidirectional"))
      (node (ref "U$9") (pin "9") (pinfunction "TP_9") (pintype "bidirectional"))
      (node (ref "U$9") (pin "9_1") (pinfunction "TP_9_1") (pintype "bidirectional"))
      (node (ref "U$9") (pin "9_2") (pinfunction "TP_9_2") (pintype "bidirectional"))
      (node (ref "U$9") (pin "9_3") (pinfunction "TP_9_3") (pintype "bidirectional"))
      (node (ref "U$9") (pin "9_4") (pinfunction "TP_9_4") (pintype "bidirectional"))
      (node (ref "U2") (pin "7") (pinfunction "GND_7") (pintype "power_in"))
      (node (ref "U2") (pin "9") (pinfunction "EXP_9") (pintype "power_in"))
      (node (ref "U2") (pin "P$1") (pinfunction "EXP_P$1") (pintype "power_in"))
      (node (ref "U2") (pin "P$2") (pinfunction "EXP_P$2") (pintype "power_in"))
      (node (ref "U2") (pin "P$3") (pinfunction "EXP_P$3") (pintype "power_in"))
      (node (ref "U2") (pin "P$4") (pinfunction "EXP_P$4") (pintype "power_in"))
      (node (ref "U2") (pin "P$5") (pinfunction "EXP_P$5") (pintype "power_in"))
      (node (ref "U2") (pin "P$6") (pinfunction "EXP_P$6") (pintype "power_in"))
      (node (ref "U3") (pin "7") (pinfunction "GND_7") (pintype "power_in"))
      (node (ref "U3") (pin "9") (pinfunction "EXP_9") (pintype "power_in"))
      (node (ref "U3") (pin "P$1") (pinfunction "EXP_P$1") (pintype "power_in"))
      (node (ref "U3") (pin "P$2") (pinfunction "EXP_P$2") (pintype "power_in"))
      (node (ref "U3") (pin "P$3") (pinfunction "EXP_P$3") (pintype "power_in"))
      (node (ref "U3") (pin "P$4") (pinfunction "EXP_P$4") (pintype "power_in"))
      (node (ref "U3") (pin "P$5") (pinfunction "EXP_P$5") (pintype "power_in"))
      (node (ref "U3") (pin "P$6") (pinfunction "EXP_P$6") (pintype "power_in"))
      (node (ref "U4") (pin "7") (pinfunction "GND_7") (pintype "power_in"))
      (node (ref "U4") (pin "9") (pinfunction "EXP_9") (pintype "power_in"))
      (node (ref "U4") (pin "P$1") (pinfunction "EXP_P$1") (pintype "power_in"))
      (node (ref "U4") (pin "P$2") (pinfunction "EXP_P$2") (pintype "power_in"))
      (node (ref "U4") (pin "P$3") (pinfunction "EXP_P$3") (pintype "power_in"))
      (node (ref "U4") (pin "P$4") (pinfunction "EXP_P$4") (pintype "power_in"))
      (node (ref "U4") (pin "P$5") (pinfunction "EXP_P$5") (pintype "power_in"))
      (node (ref "U4") (pin "P$6") (pinfunction "EXP_P$6") (pintype "power_in"))
      (node (ref "U5") (pin "7") (pinfunction "GND_7") (pintype "power_in"))
      (node (ref "U5") (pin "9") (pinfunction "EXP_9") (pintype "power_in"))
      (node (ref "U5") (pin "P$1") (pinfunction "EXP_P$1") (pintype "power_in"))
      (node (ref "U5") (pin "P$2") (pinfunction "EXP_P$2") (pintype "power_in"))
      (node (ref "U5") (pin "P$3") (pinfunction "EXP_P$3") (pintype "power_in"))
      (node (ref "U5") (pin "P$4") (pinfunction "EXP_P$4") (pintype "power_in"))
      (node (ref "U5") (pin "P$5") (pinfunction "EXP_P$5") (pintype "power_in"))
      (node (ref "U5") (pin "P$6") (pinfunction "EXP_P$6") (pintype "power_in"))
      (node (ref "U6") (pin "7") (pinfunction "GND_7") (pintype "power_in"))
      (node (ref "U6") (pin "9") (pinfunction "EXP_9") (pintype "power_in"))
      (node (ref "U6") (pin "P$1") (pinfunction "EXP_P$1") (pintype "power_in"))
      (node (ref "U6") (pin "P$2") (pinfunction "EXP_P$2") (pintype "power_in"))
      (node (ref "U6") (pin "P$3") (pinfunction "EXP_P$3") (pintype "power_in"))
      (node (ref "U6") (pin "P$4") (pinfunction "EXP_P$4") (pintype "power_in"))
      (node (ref "U6") (pin "P$5") (pinfunction "EXP_P$5") (pintype "power_in"))
      (node (ref "U6") (pin "P$6") (pinfunction "EXP_P$6") (pintype "power_in"))
      (node (ref "U7") (pin "7") (pinfunction "GND_7") (pintype "power_in"))
      (node (ref "U7") (pin "9") (pinfunction "EXP_9") (pintype "power_in"))
      (node (ref "U7") (pin "P$1") (pinfunction "EXP_P$1") (pintype "power_in"))
      (node (ref "U7") (pin "P$2") (pinfunction "EXP_P$2") (pintype "power_in"))
      (node (ref "U7") (pin "P$3") (pinfunction "EXP_P$3") (pintype "power_in"))
      (node (ref "U7") (pin "P$4") (pinfunction "EXP_P$4") (pintype "power_in"))
      (node (ref "U7") (pin "P$5") (pinfunction "EXP_P$5") (pintype "power_in"))
      (node (ref "U7") (pin "P$6") (pinfunction "EXP_P$6") (pintype "power_in"))
      (node (ref "U8") (pin "7") (pinfunction "GND_7") (pintype "power_in"))
      (node (ref "U8") (pin "9") (pinfunction "EXP_9") (pintype "power_in"))
      (node (ref "U8") (pin "P$1") (pinfunction "EXP_P$1") (pintype "power_in"))
      (node (ref "U8") (pin "P$2") (pinfunction "EXP_P$2") (pintype "power_in"))
      (node (ref "U8") (pin "P$3") (pinfunction "EXP_P$3") (pintype "power_in"))
      (node (ref "U8") (pin "P$4") (pinfunction "EXP_P$4") (pintype "power_in"))
      (node (ref "U8") (pin "P$5") (pinfunction "EXP_P$5") (pintype "power_in"))
      (node (ref "U8") (pin "P$6") (pinfunction "EXP_P$6") (pintype "power_in"))
    )
    (net (code "20") (name "MAGNETO_SCL") (class "Default")
      (node (ref "U$13") (pin "18") (pinfunction "18_18") (pintype "bidirectional"))
      (node (ref "U$14") (pin "17") (pinfunction "17_17") (pintype "bidirectional"))
    )
    (net (code "21") (name "MAGNETO_SDA") (class "Default")
      (node (ref "U$13") (pin "16") (pinfunction "16_16") (pintype "bidirectional"))
      (node (ref "U$14") (pin "15") (pinfunction "15_15") (pintype "bidirectional"))
    )
    (net (code "22") (name "MAGNETO_SUPPLY") (class "Default")
      (node (ref "U$13") (pin "20") (pinfunction "20_20") (pintype "bidirectional"))
      (node (ref "U$14") (pin "19") (pinfunction "19_19") (pintype "bidirectional"))
    )
    (net (code "23") (name "MR_3V8") (class "Default")
      (node (ref "R28") (pin "1") (pinfunction "1_1") (pintype "passive"))
      (node (ref "U$5") (pin "17") (pinfunction "17_17") (pintype "bidirectional"))
    )
    (net (code "24") (name "MR_3V8'") (class "Default")
      (node (ref "R72") (pin "1") (pinfunction "1_1") (pintype "passive"))
      (node (ref "U$5") (pin "14") (pinfunction "14_14") (pintype "bidirectional"))
    )
    (net (code "25") (name "MR_5V5") (class "Default")
      (node (ref "R39") (pin "1") (pinfunction "1_1") (pintype "passive"))
      (node (ref "U$5") (pin "18") (pinfunction "18_18") (pintype "bidirectional"))
    )
    (net (code "26") (name "MR_5V5'") (class "Default")
      (node (ref "R61") (pin "1") (pinfunction "1_1") (pintype "passive"))
      (node (ref "U$5") (pin "16") (pinfunction "16_16") (pintype "bidirectional"))
    )
    (net (code "27") (name "MR_6V6") (class "Default")
      (node (ref "R50") (pin "1") (pinfunction "1_1") (pintype "passive"))
      (node (ref "U$5") (pin "15") (pinfunction "15_15") (pintype "bidirectional"))
    )
    (net (code "28") (name "MR_7V4") (class "Default")
      (node (ref "R83") (pin "1") (pinfunction "1_1") (pintype "passive"))
      (node (ref "U$5") (pin "20") (pinfunction "20_20") (pintype "bidirectional"))
    )
    (net (code "29") (name "MR_13V") (class "Default")
      (node (ref "R92") (pin "1") (pinfunction "1_1") (pintype "passive"))
      (node (ref "U$5") (pin "13") (pinfunction "13_13") (pintype "bidirectional"))
    )
    (net (code "30") (name "Net-(C16-Pad2)") (class "Default")
      (node (ref "C16") (pin "2") (pinfunction "2_2") (pintype "passive"))
      (node (ref "R18") (pin "1") (pinfunction "1_1") (pintype "passive"))
    )
    (net (code "31") (name "Net-(C35-Pad2)") (class "Default")
      (node (ref "C35") (pin "2") (pinfunction "2_2") (pintype "passive"))
      (node (ref "R33") (pin "1") (pinfunction "1_1") (pintype "passive"))
    )
    (net (code "32") (name "Net-(C50-Pad2)") (class "Default")
      (node (ref "C50") (pin "2") (pinfunction "2_2") (pintype "passive"))
      (node (ref "R44") (pin "1") (pinfunction "1_1") (pintype "passive"))
    )
    (net (code "33") (name "Net-(C65-Pad2)") (class "Default")
      (node (ref "C65") (pin "2") (pinfunction "2_2") (pintype "passive"))
      (node (ref "R55") (pin "1") (pinfunction "1_1") (pintype "passive"))
    )
    (net (code "34") (name "Net-(C80-Pad2)") (class "Default")
      (node (ref "C80") (pin "2") (pinfunction "2_2") (pintype "passive"))
      (node (ref "R66") (pin "1") (pinfunction "1_1") (pintype "passive"))
    )
    (net (code "35") (name "Net-(C95-Pad2)") (class "Default")
      (node (ref "C95") (pin "2") (pinfunction "2_2") (pintype "passive"))
      (node (ref "R77") (pin "1") (pinfunction "1_1") (pintype "passive"))
    )
    (net (code "36") (name "Net-(C110-Pad2)") (class "Default")
      (node (ref "C110") (pin "2") (pinfunction "2_2") (pintype "passive"))
      (node (ref "R86") (pin "1") (pinfunction "1_1") (pintype "passive"))
    )
    (net (code "37") (name "Net-(LED1-PadA)") (class "Default")
      (node (ref "LED1") (pin "A") (pinfunction "A_A") (pintype "passive"))
      (node (ref "R2") (pin "1") (pinfunction "1_1") (pintype "passive"))
    )
    (net (code "38") (name "Net-(LED2-PadA)") (class "Default")
      (node (ref "LED2") (pin "A") (pinfunction "A_A") (pintype "passive"))
      (node (ref "R7") (pin "1") (pinfunction "1_1") (pintype "passive"))
    )
    (net (code "39") (name "Net-(LED3-PadA)") (class "Default")
      (node (ref "LED3") (pin "A") (pinfunction "A_A") (pintype "passive"))
      (node (ref "R6") (pin "1") (pinfunction "1_1") (pintype "passive"))
    )
    (net (code "40") (name "Net-(LED4-PadA)") (class "Default")
      (node (ref "LED4") (pin "A") (pinfunction "A_A") (pintype "passive"))
      (node (ref "R3") (pin "1") (pinfunction "1_1") (pintype "passive"))
    )
    (net (code "41") (name "Net-(LED5-PadA)") (class "Default")
      (node (ref "LED5") (pin "A") (pinfunction "A_A") (pintype "passive"))
      (node (ref "R4") (pin "1") (pinfunction "1_1") (pintype "passive"))
    )
    (net (code "42") (name "Net-(LED6-PadA)") (class "Default")
      (node (ref "LED6") (pin "A") (pinfunction "A_A") (pintype "passive"))
      (node (ref "R5") (pin "1") (pinfunction "1_1") (pintype "passive"))
    )
    (net (code "43") (name "Net-(LED7-PadA)") (class "Default")
      (node (ref "LED7") (pin "A") (pinfunction "A_A") (pintype "passive"))
      (node (ref "R1") (pin "1") (pinfunction "1_1") (pintype "passive"))
    )
    (net (code "44") (name "Net-(Q1-G)") (class "Default")
      (node (ref "C23") (pin "1") (pinfunction "1_1") (pintype "passive"))
      (node (ref "Q1") (pin "1") (pinfunction "G_1") (pintype "passive"))
      (node (ref "Q2") (pin "2") (pinfunction "S_2") (pintype "passive"))
      (node (ref "R23") (pin "2") (pinfunction "2_2") (pintype "passive"))
      (node (ref "R24") (pin "1") (pinfunction "1_1") (pintype "passive"))
    )
    (net (code "45") (name "Net-(Q2-D)") (class "Default")
      (node (ref "C25") (pin "1") (pinfunction "1_1") (pintype "passive"))
      (node (ref "Q2") (pin "3") (pinfunction "D_3") (pintype "passive"))
      (node (ref "U$6") (pin "3") (pinfunction "~{MR}_3") (pintype "bidirectional"))
    )
    (net (code "46") (name "Net-(Q2-G)") (class "Default")
      (node (ref "C24") (pin "1") (pinfunction "1_1") (pintype "passive"))
      (node (ref "Q2") (pin "1") (pinfunction "G_1") (pintype "passive"))
      (node (ref "R25") (pin "2") (pinfunction "2_2") (pintype "passive"))
      (node (ref "R28") (pin "2") (pinfunction "2_2") (pintype "passive"))
    )
    (net (code "47") (name "Net-(Q5-G)") (class "Default")
      (node (ref "C42") (pin "1") (pinfunction "1_1") (pintype "passive"))
      (node (ref "Q5") (pin "1") (pinfunction "G_1") (pintype "passive"))
      (node (ref "Q6") (pin "2") (pinfunction "S_2") (pintype "passive"))
      (node (ref "R34") (pin "2") (pinfunction "2_2") (pintype "passive"))
      (node (ref "R35") (pin "1") (pinfunction "1_1") (pintype "passive"))
    )
    (net (code "48") (name "Net-(Q6-D)") (class "Default")
      (node (ref "C44") (pin "1") (pinfunction "1_1") (pintype "passive"))
      (node (ref "Q6") (pin "3") (pinfunction "D_3") (pintype "passive"))
      (node (ref "U$7") (pin "3") (pinfunction "~{MR}_3") (pintype "bidirectional"))
    )
    (net (code "49") (name "Net-(Q6-G)") (class "Default")
      (node (ref "C43") (pin "1") (pinfunction "1_1") (pintype "passive"))
      (node (ref "Q6") (pin "1") (pinfunction "G_1") (pintype "passive"))
      (node (ref "R36") (pin "2") (pinfunction "2_2") (pintype "passive"))
      (node (ref "R39") (pin "2") (pinfunction "2_2") (pintype "passive"))
    )
    (net (code "50") (name "Net-(Q7-G)") (class "Default")
      (node (ref "C57") (pin "1") (pinfunction "1_1") (pintype "passive"))
      (node (ref "Q7") (pin "1") (pinfunction "G_1") (pintype "passive"))
      (node (ref "Q8") (pin "2") (pinfunction "S_2") (pintype "passive"))
      (node (ref "R45") (pin "2") (pinfunction "2_2") (pintype "passive"))
      (node (ref "R46") (pin "1") (pinfunction "1_1") (pintype "passive"))
    )
    (net (code "51") (name "Net-(Q8-D)") (class "Default")
      (node (ref "C59") (pin "1") (pinfunction "1_1") (pintype "passive"))
      (node (ref "Q8") (pin "3") (pinfunction "D_3") (pintype "passive"))
      (node (ref "U$8") (pin "3") (pinfunction "~{MR}_3") (pintype "bidirectional"))
    )
    (net (code "52") (name "Net-(Q8-G)") (class "Default")
      (node (ref "C58") (pin "1") (pinfunction "1_1") (pintype "passive"))
      (node (ref "Q8") (pin "1") (pinfunction "G_1") (pintype "passive"))
      (node (ref "R47") (pin "2") (pinfunction "2_2") (pintype "passive"))
      (node (ref "R50") (pin "2") (pinfunction "2_2") (pintype "passive"))
    )
    (net (code "53") (name "Net-(Q10-D)") (class "Default")
      (node (ref "C74") (pin "1") (pinfunction "1_1") (pintype "passive"))
      (node (ref "Q10") (pin "3") (pinfunction "D_3") (pintype "passive"))
      (node (ref "U$9") (pin "3") (pinfunction "~{MR}_3") (pintype "bidirectional"))
    )
    (net (code "54") (name "Net-(Q10-G)") (class "Default")
      (node (ref "C73") (pin "1") (pinfunction "1_1") (pintype "passive"))
      (node (ref "Q10") (pin "1") (pinfunction "G_1") (pintype "passive"))
      (node (ref "R58") (pin "2") (pinfunction "2_2") (pintype "passive"))
      (node (ref "R61") (pin "2") (pinfunction "2_2") (pintype "passive"))
    )
    (net (code "55") (name "Net-(Q10-S)") (class "Default")
      (node (ref "C72") (pin "1") (pinfunction "1_1") (pintype "passive"))
      (node (ref "Q10") (pin "2") (pinfunction "S_2") (pintype "passive"))
      (node (ref "Q9") (pin "1") (pinfunction "G_1") (pintype "passive"))
      (node (ref "R56") (pin "2") (pinfunction "2_2") (pintype "passive"))
      (node (ref "R57") (pin "1") (pinfunction "1_1") (pintype "passive"))
    )
    (net (code "56") (name "Net-(Q11-G)") (class "Default")
      (node (ref "C87") (pin "1") (pinfunction "1_1") (pintype "passive"))
      (node (ref "Q11") (pin "1") (pinfunction "G_1") (pintype "passive"))
      (node (ref "Q12") (pin "2") (pinfunction "S_2") (pintype "passive"))
      (node (ref "R67") (pin "2") (pinfunction "2_2") (pintype "passive"))
      (node (ref "R68") (pin "1") (pinfunction "1_1") (pintype "passive"))
    )
    (net (code "57") (name "Net-(Q12-D)") (class "Default")
      (node (ref "C89") (pin "1") (pinfunction "1_1") (pintype "passive"))
      (node (ref "Q12") (pin "3") (pinfunction "D_3") (pintype "passive"))
      (node (ref "U$10") (pin "3") (pinfunction "~{MR}_3") (pintype "bidirectional"))
    )
    (net (code "58") (name "Net-(Q12-G)") (class "Default")
      (node (ref "C88") (pin "1") (pinfunction "1_1") (pintype "passive"))
      (node (ref "Q12") (pin "1") (pinfunction "G_1") (pintype "passive"))
      (node (ref "R69") (pin "2") (pinfunction "2_2") (pintype "passive"))
      (node (ref "R72") (pin "2") (pinfunction "2_2") (pintype "passive"))
    )
    (net (code "59") (name "Net-(Q13-G)") (class "Default")
      (node (ref "C102") (pin "1") (pinfunction "1_1") (pintype "passive"))
      (node (ref "Q13") (pin "1") (pinfunction "G_1") (pintype "passive"))
      (node (ref "Q14") (pin "2") (pinfunction "S_2") (pintype "passive"))
      (node (ref "R78") (pin "2") (pinfunction "2_2") (pintype "passive"))
      (node (ref "R79") (pin "1") (pinfunction "1_1") (pintype "passive"))
    )
    (net (code "60") (name "Net-(Q14-D)") (class "Default")
      (node (ref "C104") (pin "1") (pinfunction "1_1") (pintype "passive"))
      (node (ref "Q14") (pin "3") (pinfunction "D_3") (pintype "passive"))
      (node (ref "U$11") (pin "3") (pinfunction "~{MR}_3") (pintype "bidirectional"))
    )
    (net (code "61") (name "Net-(Q14-G)") (class "Default")
      (node (ref "C103") (pin "1") (pinfunction "1_1") (pintype "passive"))
      (node (ref "Q14") (pin "1") (pinfunction "G_1") (pintype "passive"))
      (node (ref "R80") (pin "2") (pinfunction "2_2") (pintype "passive"))
      (node (ref "R83") (pin "2") (pinfunction "2_2") (pintype "passive"))
    )
    (net (code "62") (name "Net-(Q15-G)") (class "Default")
      (node (ref "C117") (pin "1") (pinfunction "1_1") (pintype "passive"))
      (node (ref "Q15") (pin "1") (pinfunction "G_1") (pintype "passive"))
      (node (ref "Q16") (pin "2") (pinfunction "S_2") (pintype "passive"))
      (node (ref "R87") (pin "2") (pinfunction "2_2") (pintype "passive"))
      (node (ref "R88") (pin "1") (pinfunction "1_1") (pintype "passive"))
    )
    (net (code "63") (name "Net-(Q16-D)") (class "Default")
      (node (ref "C119") (pin "1") (pinfunction "1_1") (pintype "passive"))
      (node (ref "Q16") (pin "3") (pinfunction "D_3") (pintype "passive"))
      (node (ref "U$12") (pin "3") (pinfunction "~{MR}_3") (pintype "bidirectional"))
    )
    (net (code "64") (name "Net-(Q16-G)") (class "Default")
      (node (ref "C118") (pin "1") (pinfunction "1_1") (pintype "passive"))
      (node (ref "Q16") (pin "1") (pinfunction "G_1") (pintype "passive"))
      (node (ref "R89") (pin "2") (pinfunction "2_2") (pintype "passive"))
      (node (ref "R92") (pin "2") (pinfunction "2_2") (pintype "passive"))
    )
    (net (code "65") (name "Net-(U$6-CWD)") (class "Default")
      (node (ref "R26") (pin "1") (pinfunction "1_1") (pintype "passive"))
      (node (ref "U$6") (pin "2") (pinfunction "CWD_2") (pintype "bidirectional"))
    )
    (net (code "66") (name "Net-(U$6-SET1)") (class "Default")
      (node (ref "R27") (pin "1") (pinfunction "1_1") (pintype "passive"))
      (node (ref "U$6") (pin "5") (pinfunction "SET1_5") (pintype "bidirectional"))
    )
    (net (code "67") (name "Net-(U$6-~{RESET})") (class "Default")
      (node (ref "R23") (pin "1") (pinfunction "1_1") (pintype "passive"))
      (node (ref "U$6") (pin "7") (pinfunction "~{WDO}_7") (pintype "bidirectional"))
      (node (ref "U$6") (pin "8") (pinfunction "~{RESET}_8") (pintype "bidirectional"))
    )
    (net (code "68") (name "Net-(U$7-CWD)") (class "Default")
      (node (ref "R37") (pin "1") (pinfunction "1_1") (pintype "passive"))
      (node (ref "U$7") (pin "2") (pinfunction "CWD_2") (pintype "bidirectional"))
    )
    (net (code "69") (name "Net-(U$7-SET1)") (class "Default")
      (node (ref "R38") (pin "1") (pinfunction "1_1") (pintype "passive"))
      (node (ref "U$7") (pin "5") (pinfunction "SET1_5") (pintype "bidirectional"))
    )
    (net (code "70") (name "Net-(U$7-~{RESET})") (class "Default")
      (node (ref "R34") (pin "1") (pinfunction "1_1") (pintype "passive"))
      (node (ref "U$7") (pin "7") (pinfunction "~{WDO}_7") (pintype "bidirectional"))
      (node (ref "U$7") (pin "8") (pinfunction "~{RESET}_8") (pintype "bidirectional"))
    )
    (net (code "71") (name "Net-(U$8-CWD)") (class "Default")
      (node (ref "R48") (pin "1") (pinfunction "1_1") (pintype "passive"))
      (node (ref "U$8") (pin "2") (pinfunction "CWD_2") (pintype "bidirectional"))
    )
    (net (code "72") (name "Net-(U$8-SET1)") (class "Default")
      (node (ref "R49") (pin "1") (pinfunction "1_1") (pintype "passive"))
      (node (ref "U$8") (pin "5") (pinfunction "SET1_5") (pintype "bidirectional"))
    )
    (net (code "73") (name "Net-(U$8-~{RESET})") (class "Default")
      (node (ref "R45") (pin "1") (pinfunction "1_1") (pintype "passive"))
      (node (ref "U$8") (pin "7") (pinfunction "~{WDO}_7") (pintype "bidirectional"))
      (node (ref "U$8") (pin "8") (pinfunction "~{RESET}_8") (pintype "bidirectional"))
    )
    (net (code "74") (name "Net-(U$9-CWD)") (class "Default")
      (node (ref "R59") (pin "1") (pinfunction "1_1") (pintype "passive"))
      (node (ref "U$9") (pin "2") (pinfunction "CWD_2") (pintype "bidirectional"))
    )
    (net (code "75") (name "Net-(U$9-SET1)") (class "Default")
      (node (ref "R60") (pin "1") (pinfunction "1_1") (pintype "passive"))
      (node (ref "U$9") (pin "5") (pinfunction "SET1_5") (pintype "bidirectional"))
    )
    (net (code "76") (name "Net-(U$9-~{RESET})") (class "Default")
      (node (ref "R56") (pin "1") (pinfunction "1_1") (pintype "passive"))
      (node (ref "U$9") (pin "7") (pinfunction "~{WDO}_7") (pintype "bidirectional"))
      (node (ref "U$9") (pin "8") (pinfunction "~{RESET}_8") (pintype "bidirectional"))
    )
    (net (code "77") (name "Net-(U$10-CWD)") (class "Default")
      (node (ref "R70") (pin "1") (pinfunction "1_1") (pintype "passive"))
      (node (ref "U$10") (pin "2") (pinfunction "CWD_2") (pintype "bidirectional"))
    )
    (net (code "78") (name "Net-(U$10-SET1)") (class "Default")
      (node (ref "R71") (pin "1") (pinfunction "1_1") (pintype "passive"))
      (node (ref "U$10") (pin "5") (pinfunction "SET1_5") (pintype "bidirectional"))
    )
    (net (code "79") (name "Net-(U$10-~{RESET})") (class "Default")
      (node (ref "R67") (pin "1") (pinfunction "1_1") (pintype "passive"))
      (node (ref "U$10") (pin "7") (pinfunction "~{WDO}_7") (pintype "bidirectional"))
      (node (ref "U$10") (pin "8") (pinfunction "~{RESET}_8") (pintype "bidirectional"))
    )
    (net (code "80") (name "Net-(U$11-CWD)") (class "Default")
      (node (ref "R81") (pin "1") (pinfunction "1_1") (pintype "passive"))
      (node (ref "U$11") (pin "2") (pinfunction "CWD_2") (pintype "bidirectional"))
    )
    (net (code "81") (name "Net-(U$11-SET1)") (class "Default")
      (node (ref "R82") (pin "1") (pinfunction "1_1") (pintype "passive"))
      (node (ref "U$11") (pin "5") (pinfunction "SET1_5") (pintype "bidirectional"))
    )
    (net (code "82") (name "Net-(U$11-~{RESET})") (class "Default")
      (node (ref "R78") (pin "1") (pinfunction "1_1") (pintype "passive"))
      (node (ref "U$11") (pin "7") (pinfunction "~{WDO}_7") (pintype "bidirectional"))
      (node (ref "U$11") (pin "8") (pinfunction "~{RESET}_8") (pintype "bidirectional"))
    )
    (net (code "83") (name "Net-(U$12-CWD)") (class "Default")
      (node (ref "R90") (pin "1") (pinfunction "1_1") (pintype "passive"))
      (node (ref "U$12") (pin "2") (pinfunction "CWD_2") (pintype "bidirectional"))
    )
    (net (code "84") (name "Net-(U$12-SET1)") (class "Default")
      (node (ref "R91") (pin "1") (pinfunction "1_1") (pintype "passive"))
      (node (ref "U$12") (pin "5") (pinfunction "SET1_5") (pintype "bidirectional"))
    )
    (net (code "85") (name "Net-(U$12-~{RESET})") (class "Default")
      (node (ref "R87") (pin "1") (pinfunction "1_1") (pintype "passive"))
      (node (ref "U$12") (pin "7") (pinfunction "~{WDO}_7") (pintype "bidirectional"))
      (node (ref "U$12") (pin "8") (pinfunction "~{RESET}_8") (pintype "bidirectional"))
    )
    (net (code "86") (name "Net-(U2-BOOT)") (class "Default")
      (node (ref "C18") (pin "1") (pinfunction "1_1") (pintype "passive"))
      (node (ref "U2") (pin "1") (pinfunction "BOOT_1") (pintype "output"))
    )
    (net (code "87") (name "Net-(U2-COMP)") (class "Default")
      (node (ref "C16") (pin "1") (pinfunction "1_1") (pintype "passive"))
      (node (ref "C17") (pin "1") (pinfunction "1_1") (pintype "passive"))
      (node (ref "U2") (pin "6") (pinfunction "COMP_6") (pintype "output"))
    )
    (net (code "88") (name "Net-(U2-PH)") (class "Default")
      (node (ref "C18") (pin "2") (pinfunction "2_2") (pintype "passive"))
      (node (ref "D3") (pin "C") (pinfunction "C_C") (pintype "passive"))
      (node (ref "L2") (pin "1") (pinfunction "1_1") (pintype "passive"))
      (node (ref "U2") (pin "8") (pinfunction "PH_8") (pintype "output"))
    )
    (net (code "89") (name "Net-(U2-SS)") (class "Default")
      (node (ref "C1") (pin "1") (pinfunction "1_1") (pintype "passive"))
      (node (ref "U2") (pin "4") (pinfunction "SS_4") (pintype "input"))
    )
    (net (code "90") (name "Net-(U2-VSENSE)") (class "Default")
      (node (ref "R14") (pin "1") (pinfunction "1_1") (pintype "passive"))
      (node (ref "R17") (pin "2") (pinfunction "2_2") (pintype "passive"))
      (node (ref "U2") (pin "5") (pinfunction "VSENSE_5") (pintype "input"))
    )
    (net (code "91") (name "Net-(U3-BOOT)") (class "Default")
      (node (ref "C37") (pin "1") (pinfunction "1_1") (pintype "passive"))
      (node (ref "U3") (pin "1") (pinfunction "BOOT_1") (pintype "output"))
    )
    (net (code "92") (name "Net-(U3-COMP)") (class "Default")
      (node (ref "C35") (pin "1") (pinfunction "1_1") (pintype "passive"))
      (node (ref "C36") (pin "1") (pinfunction "1_1") (pintype "passive"))
      (node (ref "U3") (pin "6") (pinfunction "COMP_6") (pintype "output"))
    )
    (net (code "93") (name "Net-(U3-PH)") (class "Default")
      (node (ref "C37") (pin "2") (pinfunction "2_2") (pintype "passive"))
      (node (ref "D4") (pin "C") (pinfunction "C_C") (pintype "passive"))
      (node (ref "L3") (pin "1") (pinfunction "1_1") (pintype "passive"))
      (node (ref "U3") (pin "8") (pinfunction "PH_8") (pintype "output"))
    )
    (net (code "94") (name "Net-(U3-SS)") (class "Default")
      (node (ref "C31") (pin "1") (pinfunction "1_1") (pintype "passive"))
      (node (ref "U3") (pin "4") (pinfunction "SS_4") (pintype "input"))
    )
    (net (code "95") (name "Net-(U3-VSENSE)") (class "Default")
      (node (ref "R31") (pin "1") (pinfunction "1_1") (pintype "passive"))
      (node (ref "R32") (pin "2") (pinfunction "2_2") (pintype "passive"))
      (node (ref "U3") (pin "5") (pinfunction "VSENSE_5") (pintype "input"))
    )
    (net (code "96") (name "Net-(U4-BOOT)") (class "Default")
      (node (ref "C52") (pin "1") (pinfunction "1_1") (pintype "passive"))
      (node (ref "U4") (pin "1") (pinfunction "BOOT_1") (pintype "output"))
    )
    (net (code "97") (name "Net-(U4-COMP)") (class "Default")
      (node (ref "C50") (pin "1") (pinfunction "1_1") (pintype "passive"))
      (node (ref "C51") (pin "1") (pinfunction "1_1") (pintype "passive"))
      (node (ref "U4") (pin "6") (pinfunction "COMP_6") (pintype "output"))
    )
    (net (code "98") (name "Net-(U4-PH)") (class "Default")
      (node (ref "C52") (pin "2") (pinfunction "2_2") (pintype "passive"))
      (node (ref "D5") (pin "C") (pinfunction "C_C") (pintype "passive"))
      (node (ref "L4") (pin "1") (pinfunction "1_1") (pintype "passive"))
      (node (ref "U4") (pin "8") (pinfunction "PH_8") (pintype "output"))
    )
    (net (code "99") (name "Net-(U4-SS)") (class "Default")
      (node (ref "C46") (pin "1") (pinfunction "1_1") (pintype "passive"))
      (node (ref "U4") (pin "4") (pinfunction "SS_4") (pintype "input"))
    )
    (net (code "100") (name "Net-(U4-VSENSE)") (class "Default")
      (node (ref "R42") (pin "1") (pinfunction "1_1") (pintype "passive"))
      (node (ref "R43") (pin "2") (pinfunction "2_2") (pintype "passive"))
      (node (ref "U4") (pin "5") (pinfunction "VSENSE_5") (pintype "input"))
    )
    (net (code "101") (name "Net-(U5-BOOT)") (class "Default")
      (node (ref "C67") (pin "1") (pinfunction "1_1") (pintype "passive"))
      (node (ref "U5") (pin "1") (pinfunction "BOOT_1") (pintype "output"))
    )
    (net (code "102") (name "Net-(U5-COMP)") (class "Default")
      (node (ref "C65") (pin "1") (pinfunction "1_1") (pintype "passive"))
      (node (ref "C66") (pin "1") (pinfunction "1_1") (pintype "passive"))
      (node (ref "U5") (pin "6") (pinfunction "COMP_6") (pintype "output"))
    )
    (net (code "103") (name "Net-(U5-PH)") (class "Default")
      (node (ref "C67") (pin "2") (pinfunction "2_2") (pintype "passive"))
      (node (ref "D6") (pin "C") (pinfunction "C_C") (pintype "passive"))
      (node (ref "L5") (pin "1") (pinfunction "1_1") (pintype "passive"))
      (node (ref "U5") (pin "8") (pinfunction "PH_8") (pintype "output"))
    )
    (net (code "104") (name "Net-(U5-SS)") (class "Default")
      (node (ref "C61") (pin "1") (pinfunction "1_1") (pintype "passive"))
      (node (ref "U5") (pin "4") (pinfunction "SS_4") (pintype "input"))
    )
    (net (code "105") (name "Net-(U5-VSENSE)") (class "Default")
      (node (ref "R53") (pin "1") (pinfunction "1_1") (pintype "passive"))
      (node (ref "R54") (pin "2") (pinfunction "2_2") (pintype "passive"))
      (node (ref "U5") (pin "5") (pinfunction "VSENSE_5") (pintype "input"))
    )
    (net (code "106") (name "Net-(U6-BOOT)") (class "Default")
      (node (ref "C82") (pin "1") (pinfunction "1_1") (pintype "passive"))
      (node (ref "U6") (pin "1") (pinfunction "BOOT_1") (pintype "output"))
    )
    (net (code "107") (name "Net-(U6-COMP)") (class "Default")
      (node (ref "C80") (pin "1") (pinfunction "1_1") (pintype "passive"))
      (node (ref "C81") (pin "1") (pinfunction "1_1") (pintype "passive"))
      (node (ref "U6") (pin "6") (pinfunction "COMP_6") (pintype "output"))
    )
    (net (code "108") (name "Net-(U6-PH)") (class "Default")
      (node (ref "C82") (pin "2") (pinfunction "2_2") (pintype "passive"))
      (node (ref "D7") (pin "C") (pinfunction "C_C") (pintype "passive"))
      (node (ref "L6") (pin "1") (pinfunction "1_1") (pintype "passive"))
      (node (ref "U6") (pin "8") (pinfunction "PH_8") (pintype "output"))
    )
    (net (code "109") (name "Net-(U6-SS)") (class "Default")
      (node (ref "C76") (pin "1") (pinfunction "1_1") (pintype "passive"))
      (node (ref "U6") (pin "4") (pinfunction "SS_4") (pintype "input"))
    )
    (net (code "110") (name "Net-(U6-VSENSE)") (class "Default")
      (node (ref "R64") (pin "1") (pinfunction "1_1") (pintype "passive"))
      (node (ref "R65") (pin "2") (pinfunction "2_2") (pintype "passive"))
      (node (ref "U6") (pin "5") (pinfunction "VSENSE_5") (pintype "input"))
    )
    (net (code "111") (name "Net-(U7-BOOT)") (class "Default")
      (node (ref "C97") (pin "1") (pinfunction "1_1") (pintype "passive"))
      (node (ref "U7") (pin "1") (pinfunction "BOOT_1") (pintype "output"))
    )
    (net (code "112") (name "Net-(U7-COMP)") (class "Default")
      (node (ref "C95") (pin "1") (pinfunction "1_1") (pintype "passive"))
      (node (ref "C96") (pin "1") (pinfunction "1_1") (pintype "passive"))
      (node (ref "U7") (pin "6") (pinfunction "COMP_6") (pintype "output"))
    )
    (net (code "113") (name "Net-(U7-PH)") (class "Default")
      (node (ref "C97") (pin "2") (pinfunction "2_2") (pintype "passive"))
      (node (ref "D8") (pin "C") (pinfunction "C_C") (pintype "passive"))
      (node (ref "L7") (pin "1") (pinfunction "1_1") (pintype "passive"))
      (node (ref "U7") (pin "8") (pinfunction "PH_8") (pintype "output"))
    )
    (net (code "114") (name "Net-(U7-SS)") (class "Default")
      (node (ref "C91") (pin "1") (pinfunction "1_1") (pintype "passive"))
      (node (ref "U7") (pin "4") (pinfunction "SS_4") (pintype "input"))
    )
    (net (code "115") (name "Net-(U7-VSENSE)") (class "Default")
      (node (ref "R75") (pin "1") (pinfunction "1_1") (pintype "passive"))
      (node (ref "R76") (pin "2") (pinfunction "2_2") (pintype "passive"))
      (node (ref "U7") (pin "5") (pinfunction "VSENSE_5") (pintype "input"))
    )
    (net (code "116") (name "Net-(U8-BOOT)") (class "Default")
      (node (ref "C112") (pin "1") (pinfunction "1_1") (pintype "passive"))
      (node (ref "U8") (pin "1") (pinfunction "BOOT_1") (pintype "output"))
    )
    (net (code "117") (name "Net-(U8-COMP)") (class "Default")
      (node (ref "C110") (pin "1") (pinfunction "1_1") (pintype "passive"))
      (node (ref "C111") (pin "1") (pinfunction "1_1") (pintype "passive"))
      (node (ref "U8") (pin "6") (pinfunction "COMP_6") (pintype "output"))
    )
    (net (code "118") (name "Net-(U8-PH)") (class "Default")
      (node (ref "C112") (pin "2") (pinfunction "2_2") (pintype "passive"))
      (node (ref "D2") (pin "C") (pinfunction "C_C") (pintype "passive"))
      (node (ref "L8") (pin "1") (pinfunction "1_1") (pintype "passive"))
      (node (ref "U8") (pin "8") (pinfunction "PH_8") (pintype "output"))
    )
    (net (code "119") (name "Net-(U8-SS)") (class "Default")
      (node (ref "C106") (pin "1") (pinfunction "1_1") (pintype "passive"))
      (node (ref "U8") (pin "4") (pinfunction "SS_4") (pintype "input"))
    )
    (net (code "120") (name "Net-(U8-VSENSE)") (class "Default")
      (node (ref "R84") (pin "1") (pinfunction "1_1") (pintype "passive"))
      (node (ref "R85") (pin "2") (pinfunction "2_2") (pintype "passive"))
      (node (ref "U8") (pin "5") (pinfunction "VSENSE_5") (pintype "input"))
    )
    (net (code "121") (name "PITOT_CONN") (class "Default")
      (node (ref "U$13") (pin "17") (pinfunction "17_17") (pintype "bidirectional"))
      (node (ref "U$14") (pin "18") (pinfunction "18_18") (pintype "bidirectional"))
    )
    (net (code "122") (name "PITOT_OUT") (class "Default")
      (node (ref "U$13") (pin "15") (pinfunction "15_15") (pintype "bidirectional"))
      (node (ref "U$14") (pin "16") (pinfunction "16_16") (pintype "bidirectional"))
    )
    (net (code "123") (name "PITOT_SUPPLY") (class "Default")
      (node (ref "U$13") (pin "19") (pinfunction "19_19") (pintype "bidirectional"))
      (node (ref "U$14") (pin "20") (pinfunction "20_20") (pintype "bidirectional"))
    )
    (net (code "124") (name "PRESS1") (class "Default")
      (node (ref "U$13") (pin "12") (pinfunction "12_12") (pintype "bidirectional"))
      (node (ref "U$14") (pin "11") (pinfunction "11_11") (pintype "bidirectional"))
    )
    (net (code "125") (name "PRESS2") (class "Default")
      (node (ref "U$13") (pin "13") (pinfunction "13_13") (pintype "bidirectional"))
      (node (ref "U$14") (pin "14") (pinfunction "14_14") (pintype "bidirectional"))
    )
    (net (code "126") (name "PRESS3") (class "Default")
      (node (ref "U$13") (pin "11") (pinfunction "11_11") (pintype "bidirectional"))
      (node (ref "U$14") (pin "12") (pinfunction "12_12") (pintype "bidirectional"))
    )
    (net (code "127") (name "RECO_POWER1") (class "Default")
      (node (ref "U$3") (pin "19") (pinfunction "19_19") (pintype "bidirectional"))
      (node (ref "U$4") (pin "20") (pinfunction "20_20") (pintype "bidirectional"))
    )
    (net (code "128") (name "RECO_POWER2") (class "Default")
      (node (ref "U$3") (pin "20") (pinfunction "20_20") (pintype "bidirectional"))
      (node (ref "U$4") (pin "19") (pinfunction "19_19") (pintype "bidirectional"))
    )
    (net (code "129") (name "RECO_POWER3") (class "Default")
      (node (ref "U$1") (pin "19") (pinfunction "19_19") (pintype "bidirectional"))
      (node (ref "U$2") (pin "20") (pinfunction "20_20") (pintype "bidirectional"))
    )
    (net (code "130") (name "RECO_POWER4") (class "Default")
      (node (ref "U$1") (pin "17") (pinfunction "17_17") (pintype "bidirectional"))
      (node (ref "U$2") (pin "18") (pinfunction "18_18") (pintype "bidirectional"))
    )
    (net (code "131") (name "SERVO_RECO1") (class "Default")
      (node (ref "U$3") (pin "7") (pinfunction "7_7") (pintype "bidirectional"))
      (node (ref "U$4") (pin "8") (pinfunction "8_8") (pintype "bidirectional"))
    )
    (net (code "132") (name "SERVO_RECO2") (class "Default")
      (node (ref "U$3") (pin "5") (pinfunction "5_5") (pintype "bidirectional"))
      (node (ref "U$4") (pin "6") (pinfunction "6_6") (pintype "bidirectional"))
    )
    (net (code "133") (name "SERVO_RX") (class "Default")
      (node (ref "U$13") (pin "3") (pinfunction "3_3") (pintype "bidirectional"))
      (node (ref "U$14") (pin "4") (pinfunction "4_4") (pintype "bidirectional"))
    )
    (net (code "134") (name "SERVO_TX") (class "Default")
      (node (ref "U$13") (pin "1") (pinfunction "1_1") (pintype "bidirectional"))
      (node (ref "U$14") (pin "2") (pinfunction "2_2") (pintype "bidirectional"))
    )
    (net (code "135") (name "STASZEK_OUT1") (class "Default")
      (node (ref "U$1") (pin "11") (pinfunction "11_11") (pintype "bidirectional"))
      (node (ref "U$2") (pin "12") (pinfunction "12_12") (pintype "bidirectional"))
    )
    (net (code "136") (name "STASZEK_OUT2") (class "Default")
      (node (ref "U$1") (pin "9") (pinfunction "9_9") (pintype "bidirectional"))
      (node (ref "U$2") (pin "10") (pinfunction "10_10") (pintype "bidirectional"))
    )
    (net (code "137") (name "STASZEK_OUT3") (class "Default")
      (node (ref "U$1") (pin "7") (pinfunction "7_7") (pintype "bidirectional"))
      (node (ref "U$2") (pin "8") (pinfunction "8_8") (pintype "bidirectional"))
    )
    (net (code "138") (name "STASZEK_OUT4") (class "Default")
      (node (ref "U$1") (pin "13") (pinfunction "13_13") (pintype "bidirectional"))
      (node (ref "U$2") (pin "14") (pinfunction "14_14") (pintype "bidirectional"))
    )
    (net (code "139") (name "STASZEK_RECO_PWM") (class "Default")
      (node (ref "U$3") (pin "8") (pinfunction "8_8") (pintype "bidirectional"))
      (node (ref "U$4") (pin "7") (pinfunction "7_7") (pintype "bidirectional"))
    )
    (net (code "140") (name "STASZEK_SERVO1") (class "Default")
      (node (ref "U$1") (pin "8") (pinfunction "8_8") (pintype "bidirectional"))
      (node (ref "U$2") (pin "7") (pinfunction "7_7") (pintype "bidirectional"))
    )
    (net (code "141") (name "STASZEK_SERVO2") (class "Default")
      (node (ref "U$1") (pin "10") (pinfunction "10_10") (pintype "bidirectional"))
      (node (ref "U$2") (pin "9") (pinfunction "9_9") (pintype "bidirectional"))
    )
    (net (code "142") (name "STASZEK_SERVO3") (class "Default")
      (node (ref "U$13") (pin "2") (pinfunction "2_2") (pintype "bidirectional"))
      (node (ref "U$14") (pin "1") (pinfunction "1_1") (pintype "bidirectional"))
    )
    (net (code "143") (name "STASZEK_SERVO4") (class "Default")
      (node (ref "U$13") (pin "4") (pinfunction "4_4") (pintype "bidirectional"))
      (node (ref "U$14") (pin "3") (pinfunction "3_3") (pintype "bidirectional"))
    )
    (net (code "144") (name "SUPPLY") (class "Default")
      (node (ref "C107") (pin "1") (pinfunction "1_1") (pintype "passive"))
      (node (ref "C108") (pin "1") (pinfunction "1_1") (pintype "passive"))
      (node (ref "C109") (pin "1") (pinfunction "1_1") (pintype "passive"))
      (node (ref "C13") (pin "1") (pinfunction "1_1") (pintype "passive"))
      (node (ref "C14") (pin "1") (pinfunction "1_1") (pintype "passive"))
      (node (ref "C15") (pin "1") (pinfunction "1_1") (pintype "passive"))
      (node (ref "C2") (pin "1") (pinfunction "+_1") (pintype "passive"))
      (node (ref "C3") (pin "1") (pinfunction "+_1") (pintype "passive"))
      (node (ref "C32") (pin "1") (pinfunction "1_1") (pintype "passive"))
      (node (ref "C33") (pin "1") (pinfunction "1_1") (pintype "passive"))
      (node (ref "C34") (pin "1") (pinfunction "1_1") (pintype "passive"))
      (node (ref "C47") (pin "1") (pinfunction "1_1") (pintype "passive"))
      (node (ref "C48") (pin "1") (pinfunction "1_1") (pintype "passive"))
      (node (ref "C49") (pin "1") (pinfunction "1_1") (pintype "passive"))
      (node (ref "C62") (pin "1") (pinfunction "1_1") (pintype "passive"))
      (node (ref "C63") (pin "1") (pinfunction "1_1") (pintype "passive"))
      (node (ref "C64") (pin "1") (pinfunction "1_1") (pintype "passive"))
      (node (ref "C77") (pin "1") (pinfunction "1_1") (pintype "passive"))
      (node (ref "C78") (pin "1") (pinfunction "1_1") (pintype "passive"))
      (node (ref "C79") (pin "1") (pinfunction "1_1") (pintype "passive"))
      (node (ref "C92") (pin "1") (pinfunction "1_1") (pintype "passive"))
      (node (ref "C93") (pin "1") (pinfunction "1_1") (pintype "passive"))
      (node (ref "C94") (pin "1") (pinfunction "1_1") (pintype "passive"))
      (node (ref "J3") (pin "1") (pinfunction "1_1") (pintype "bidirectional"))
      (node (ref "J3") (pin "10") (pinfunction "10_10") (pintype "bidirectional"))
      (node (ref "J3") (pin "3") (pinfunction "3_3") (pintype "bidirectional"))
      (node (ref "J3") (pin "5") (pinfunction "5_5") (pintype "bidirectional"))
      (node (ref "J3") (pin "7") (pinfunction "7_7") (pintype "bidirectional"))
      (node (ref "J3") (pin "8") (pinfunction "8_8") (pintype "bidirectional"))
      (node (ref "J3") (pin "9") (pinfunction "9_9") (pintype "bidirectional"))
      (node (ref "R10") (pin "2") (pinfunction "2_2") (pintype "passive"))
      (node (ref "R12") (pin "2") (pinfunction "2_2") (pintype "passive"))
      (node (ref "R29") (pin "2") (pinfunction "2_2") (pintype "passive"))
      (node (ref "R40") (pin "2") (pinfunction "2_2") (pintype "passive"))
      (node (ref "R51") (pin "2") (pinfunction "2_2") (pintype "passive"))
      (node (ref "R62") (pin "2") (pinfunction "2_2") (pintype "passive"))
      (node (ref "R73") (pin "2") (pinfunction "2_2") (pintype "passive"))
      (node (ref "U2") (pin "2") (pinfunction "VIN_2") (pintype "input"))
      (node (ref "U3") (pin "2") (pinfunction "VIN_2") (pintype "input"))
      (node (ref "U4") (pin "2") (pinfunction "VIN_2") (pintype "input"))
      (node (ref "U5") (pin "2") (pinfunction "VIN_2") (pintype "input"))
      (node (ref "U6") (pin "2") (pinfunction "VIN_2") (pintype "input"))
      (node (ref "U7") (pin "2") (pinfunction "VIN_2") (pintype "input"))
      (node (ref "U8") (pin "2") (pinfunction "VIN_2") (pintype "input"))
    )
    (net (code "145") (name "SYSTEM_SUPPLY") (class "Default")
      (node (ref "U$3") (pin "11") (pinfunction "11_11") (pintype "bidirectional"))
      (node (ref "U$3") (pin "12") (pinfunction "12_12") (pintype "bidirectional"))
      (node (ref "U$4") (pin "11") (pinfunction "11_11") (pintype "bidirectional"))
      (node (ref "U$4") (pin "12") (pinfunction "12_12") (pintype "bidirectional"))
    )
    (net (code "146") (name "TEMP1") (class "Default")
      (node (ref "U$13") (pin "9") (pinfunction "9_9") (pintype "bidirectional"))
      (node (ref "U$14") (pin "10") (pinfunction "10_10") (pintype "bidirectional"))
    )
    (net (code "147") (name "TEMP2") (class "Default")
      (node (ref "U$13") (pin "7") (pinfunction "7_7") (pintype "bidirectional"))
      (node (ref "U$14") (pin "8") (pinfunction "8_8") (pintype "bidirectional"))
    )
    (net (code "148") (name "TEMP3") (class "Default")
      (node (ref "U$13") (pin "5") (pinfunction "5_5") (pintype "bidirectional"))
      (node (ref "U$14") (pin "6") (pinfunction "6_6") (pintype "bidirectional"))
    )
    (net (code "149") (name "WDI_3V8") (class "Default")
      (node (ref "U$5") (pin "12") (pinfunction "12_12") (pintype "bidirectional"))
      (node (ref "U$6") (pin "6") (pinfunction "WDI_6") (pintype "bidirectional"))
    )
    (net (code "150") (name "WDI_3V8'") (class "Default")
      (node (ref "U$10") (pin "6") (pinfunction "WDI_6") (pintype "bidirectional"))
      (node (ref "U$5") (pin "5") (pinfunction "5_5") (pintype "bidirectional"))
    )
    (net (code "151") (name "WDI_5V5") (class "Default")
      (node (ref "U$5") (pin "9") (pinfunction "9_9") (pintype "bidirectional"))
      (node (ref "U$7") (pin "6") (pinfunction "WDI_6") (pintype "bidirectional"))
    )
    (net (code "152") (name "WDI_5V5'") (class "Default")
      (node (ref "U$5") (pin "7") (pinfunction "7_7") (pintype "bidirectional"))
      (node (ref "U$9") (pin "6") (pinfunction "WDI_6") (pintype "bidirectional"))
    )
    (net (code "153") (name "WDI_6V6") (class "Default")
      (node (ref "U$5") (pin "10") (pinfunction "10_10") (pintype "bidirectional"))
      (node (ref "U$8") (pin "6") (pinfunction "WDI_6") (pintype "bidirectional"))
    )
    (net (code "154") (name "WDI_7V4") (class "Default")
      (node (ref "U$11") (pin "6") (pinfunction "WDI_6") (pintype "bidirectional"))
      (node (ref "U$5") (pin "11") (pinfunction "11_11") (pintype "bidirectional"))
    )
    (net (code "155") (name "WDI_13V") (class "Default")
      (node (ref "U$12") (pin "6") (pinfunction "WDI_6") (pintype "bidirectional"))
      (node (ref "U$5") (pin "8") (pinfunction "8_8") (pintype "bidirectional"))
    )
    (net (code "156") (name "WDO_3V8") (class "Default")
      (node (ref "Q1") (pin "3") (pinfunction "D_3") (pintype "passive"))
    )
    (net (code "157") (name "WDO_3V8'") (class "Default")
      (node (ref "C8") (pin "1") (pinfunction "1_1") (pintype "passive"))
      (node (ref "Q11") (pin "3") (pinfunction "D_3") (pintype "passive"))
      (node (ref "R62") (pin "1") (pinfunction "1_1") (pintype "passive"))
      (node (ref "R63") (pin "2") (pinfunction "2_2") (pintype "passive"))
      (node (ref "U6") (pin "3") (pinfunction "EN_3") (pintype "input"))
    )
    (net (code "158") (name "WDO_5V1") (class "Default")
      (node (ref "C5") (pin "1") (pinfunction "1_1") (pintype "passive"))
      (node (ref "R12") (pin "1") (pinfunction "1_1") (pintype "passive"))
      (node (ref "R13") (pin "2") (pinfunction "2_2") (pintype "passive"))
      (node (ref "U2") (pin "3") (pinfunction "EN_3") (pintype "input"))
    )
    (net (code "159") (name "WDO_5V5") (class "Default")
      (node (ref "C4") (pin "1") (pinfunction "1_1") (pintype "passive"))
      (node (ref "Q5") (pin "3") (pinfunction "D_3") (pintype "passive"))
      (node (ref "R29") (pin "1") (pinfunction "1_1") (pintype "passive"))
      (node (ref "R30") (pin "2") (pinfunction "2_2") (pintype "passive"))
      (node (ref "U3") (pin "3") (pinfunction "EN_3") (pintype "input"))
    )
    (net (code "160") (name "WDO_5V5'") (class "Default")
      (node (ref "C7") (pin "1") (pinfunction "1_1") (pintype "passive"))
      (node (ref "Q9") (pin "3") (pinfunction "D_3") (pintype "passive"))
      (node (ref "R51") (pin "1") (pinfunction "1_1") (pintype "passive"))
      (node (ref "R52") (pin "2") (pinfunction "2_2") (pintype "passive"))
      (node (ref "U5") (pin "3") (pinfunction "EN_3") (pintype "input"))
    )
    (net (code "161") (name "WDO_6V6") (class "Default")
      (node (ref "C6") (pin "1") (pinfunction "1_1") (pintype "passive"))
      (node (ref "Q7") (pin "3") (pinfunction "D_3") (pintype "passive"))
      (node (ref "R40") (pin "1") (pinfunction "1_1") (pintype "passive"))
      (node (ref "R41") (pin "2") (pinfunction "2_2") (pintype "passive"))
      (node (ref "U4") (pin "3") (pinfunction "EN_3") (pintype "input"))
    )
    (net (code "162") (name "WDO_7V4") (class "Default")
      (node (ref "C9") (pin "1") (pinfunction "1_1") (pintype "passive"))
      (node (ref "Q13") (pin "3") (pinfunction "D_3") (pintype "passive"))
      (node (ref "R73") (pin "1") (pinfunction "1_1") (pintype "passive"))
      (node (ref "R74") (pin "2") (pinfunction "2_2") (pintype "passive"))
      (node (ref "U7") (pin "3") (pinfunction "EN_3") (pintype "input"))
    )
    (net (code "163") (name "WDO_13V") (class "Default")
      (node (ref "C10") (pin "1") (pinfunction "1_1") (pintype "passive"))
      (node (ref "Q15") (pin "3") (pinfunction "D_3") (pintype "passive"))
      (node (ref "R10") (pin "1") (pinfunction "1_1") (pintype "passive"))
      (node (ref "R11") (pin "2") (pinfunction "2_2") (pintype "passive"))
      (node (ref "U8") (pin "3") (pinfunction "EN_3") (pintype "input"))
    )
  )
)
